# PDB_Schem.net
KiCad netlist of a schematic drawn in Altium Designer
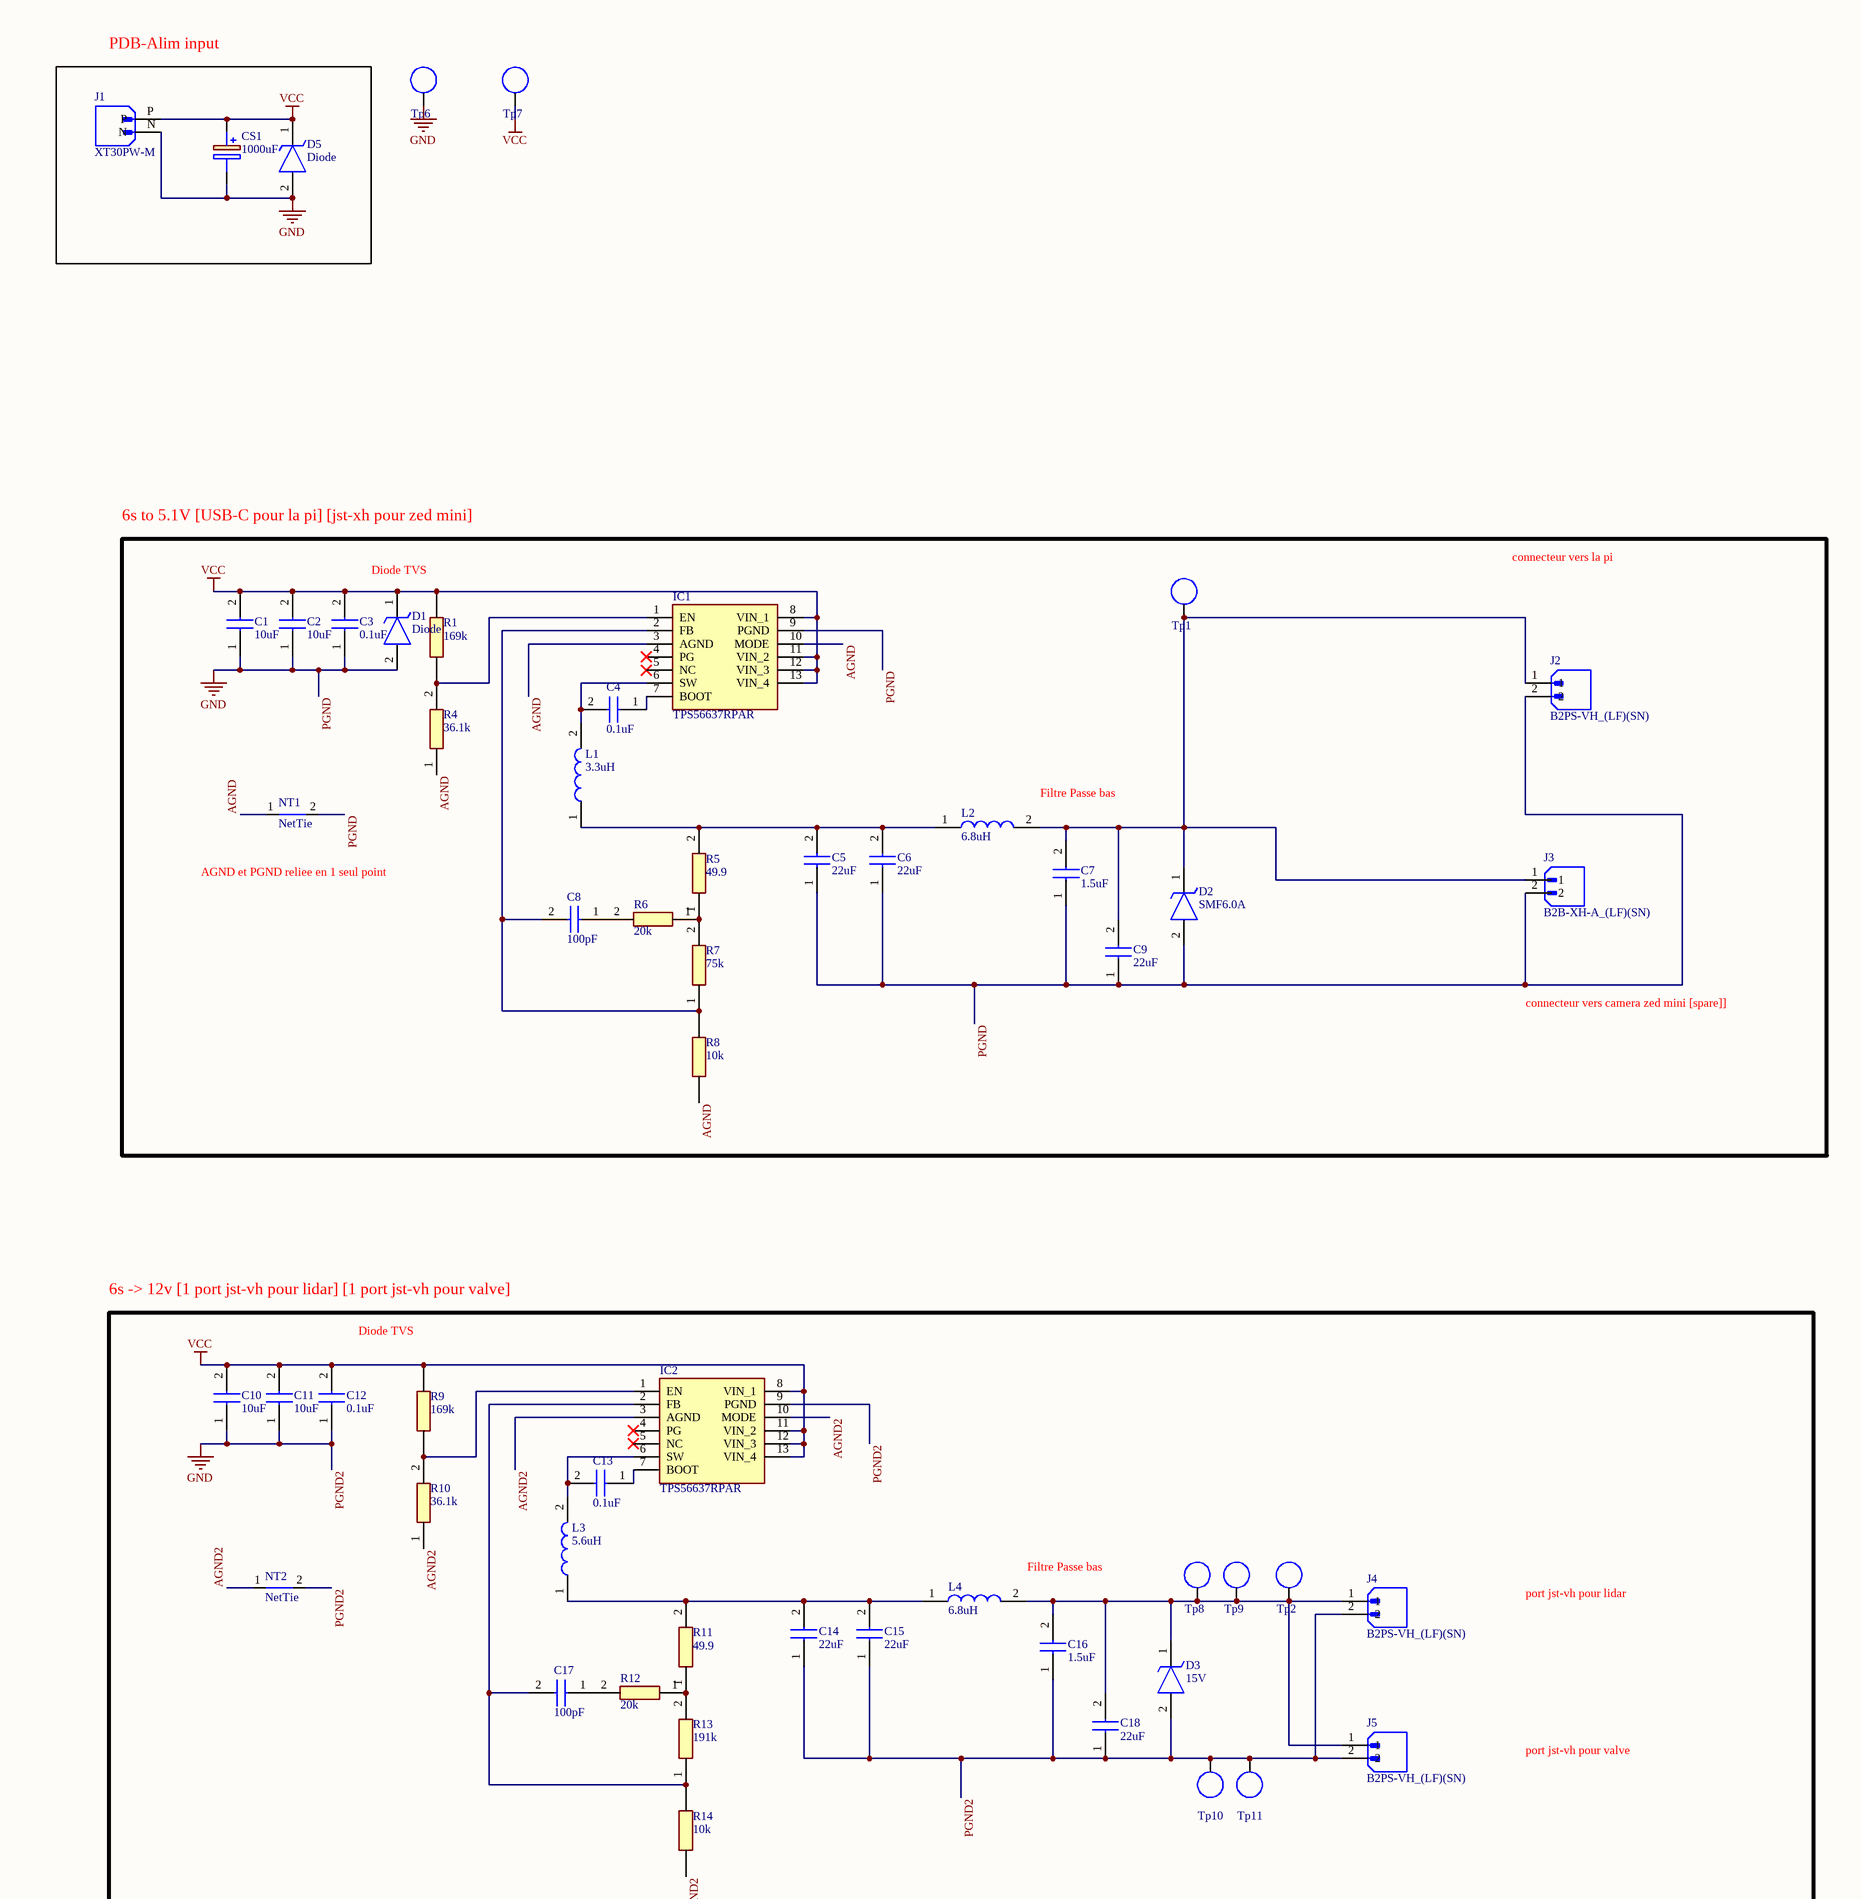
[diagram p0: PDB Schem.SchDoc, top]
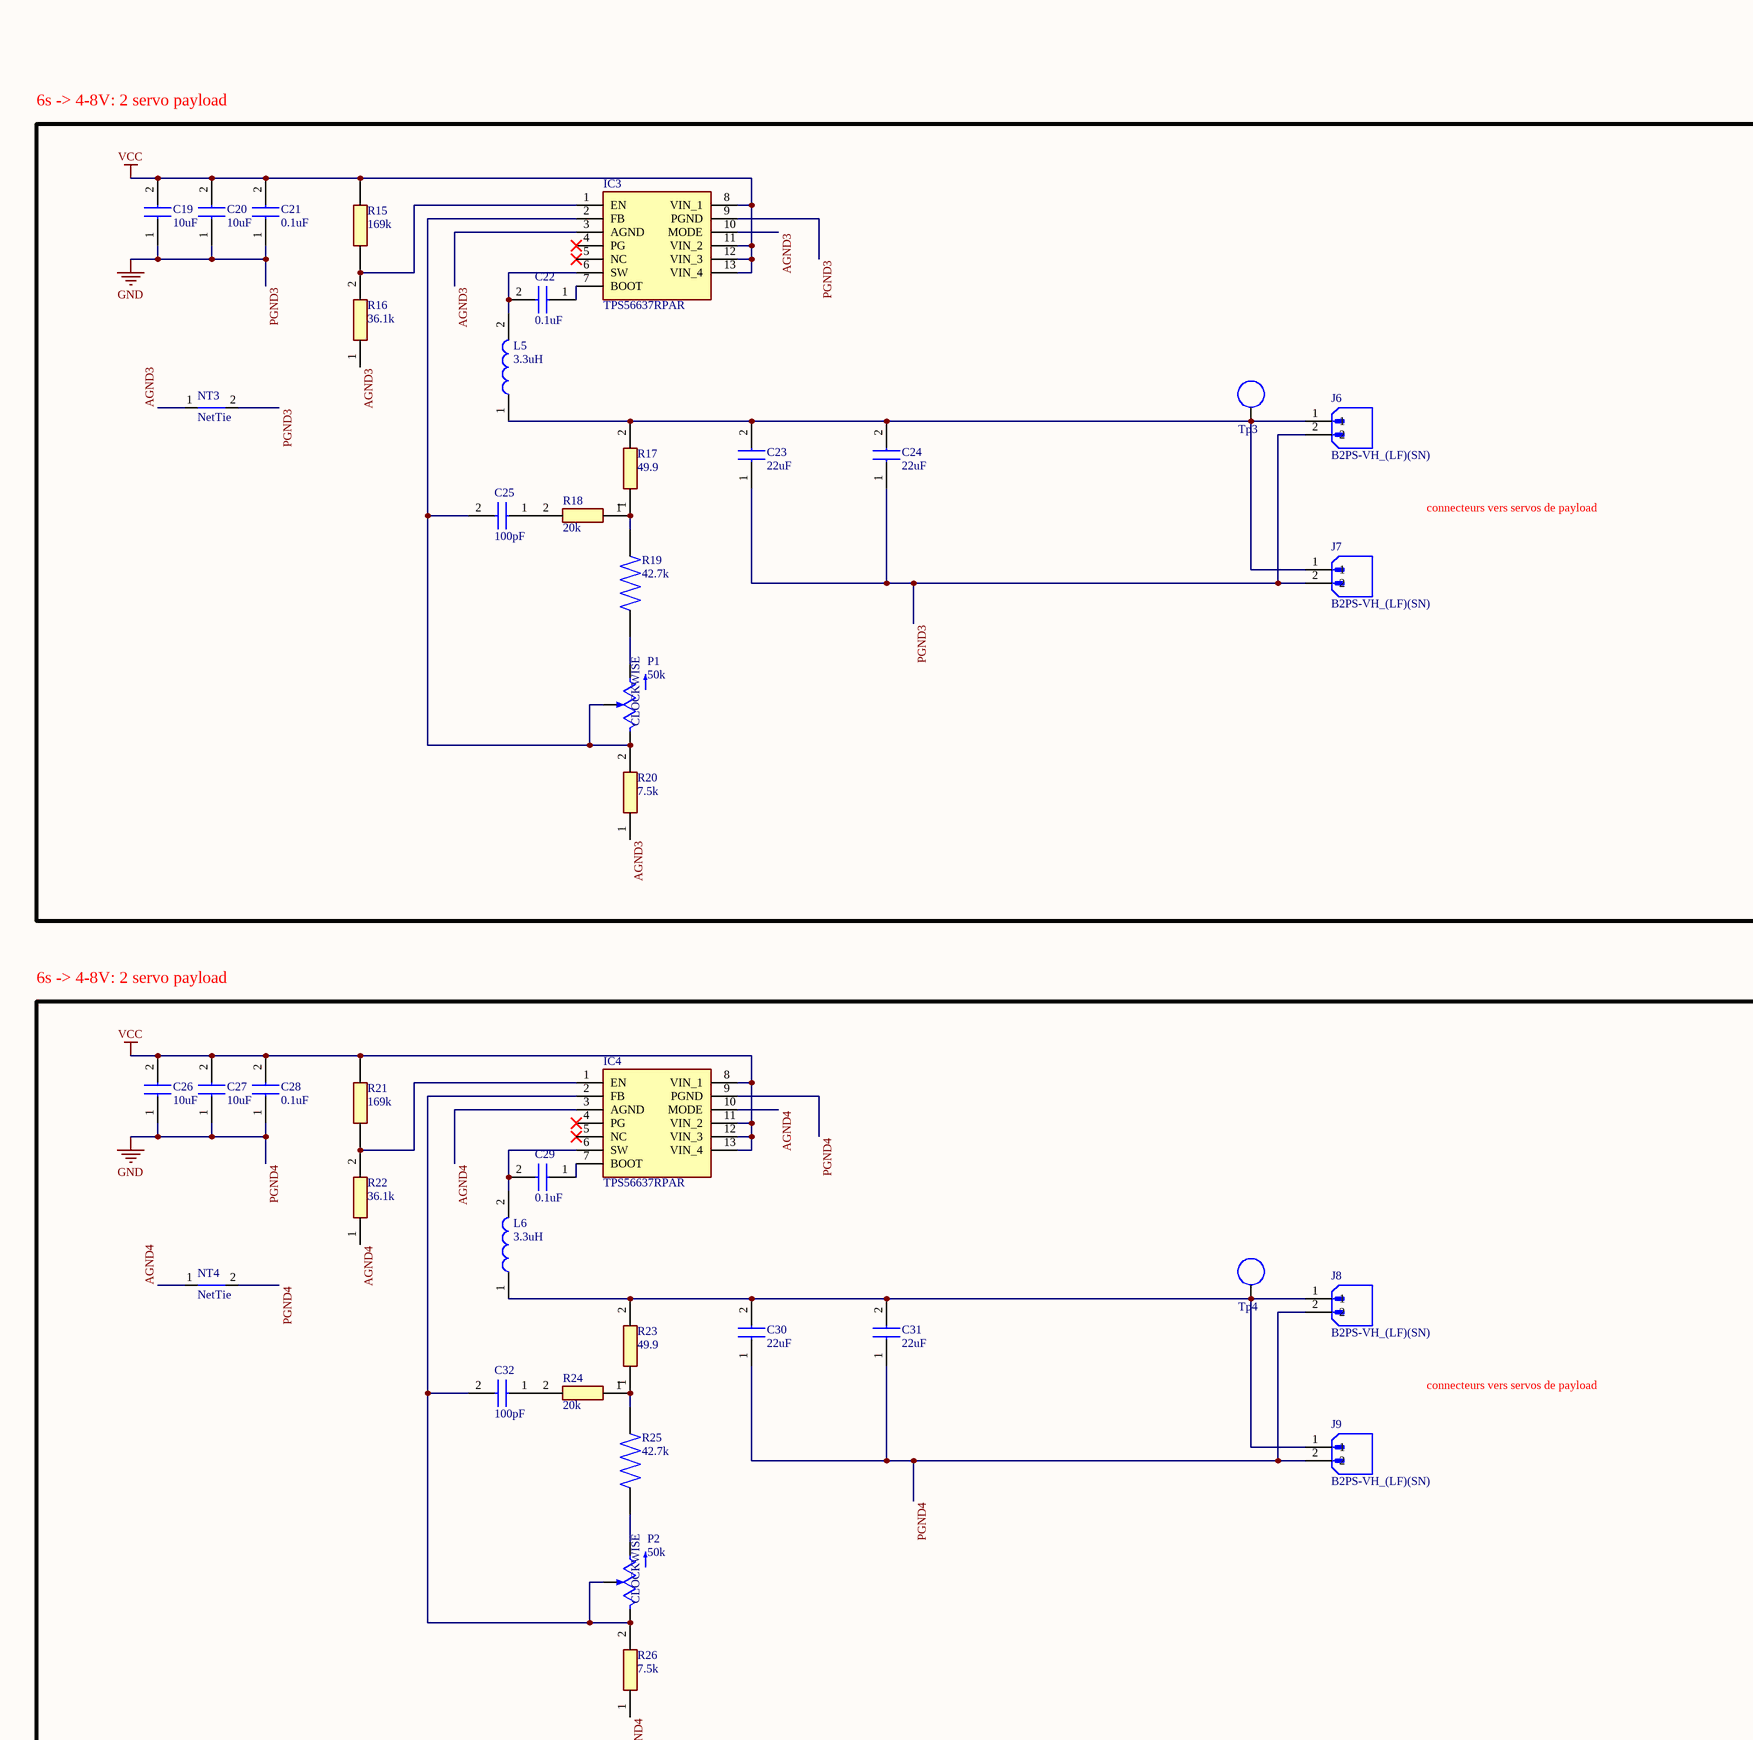
[diagram p1: PDB Schem.SchDoc, centre]
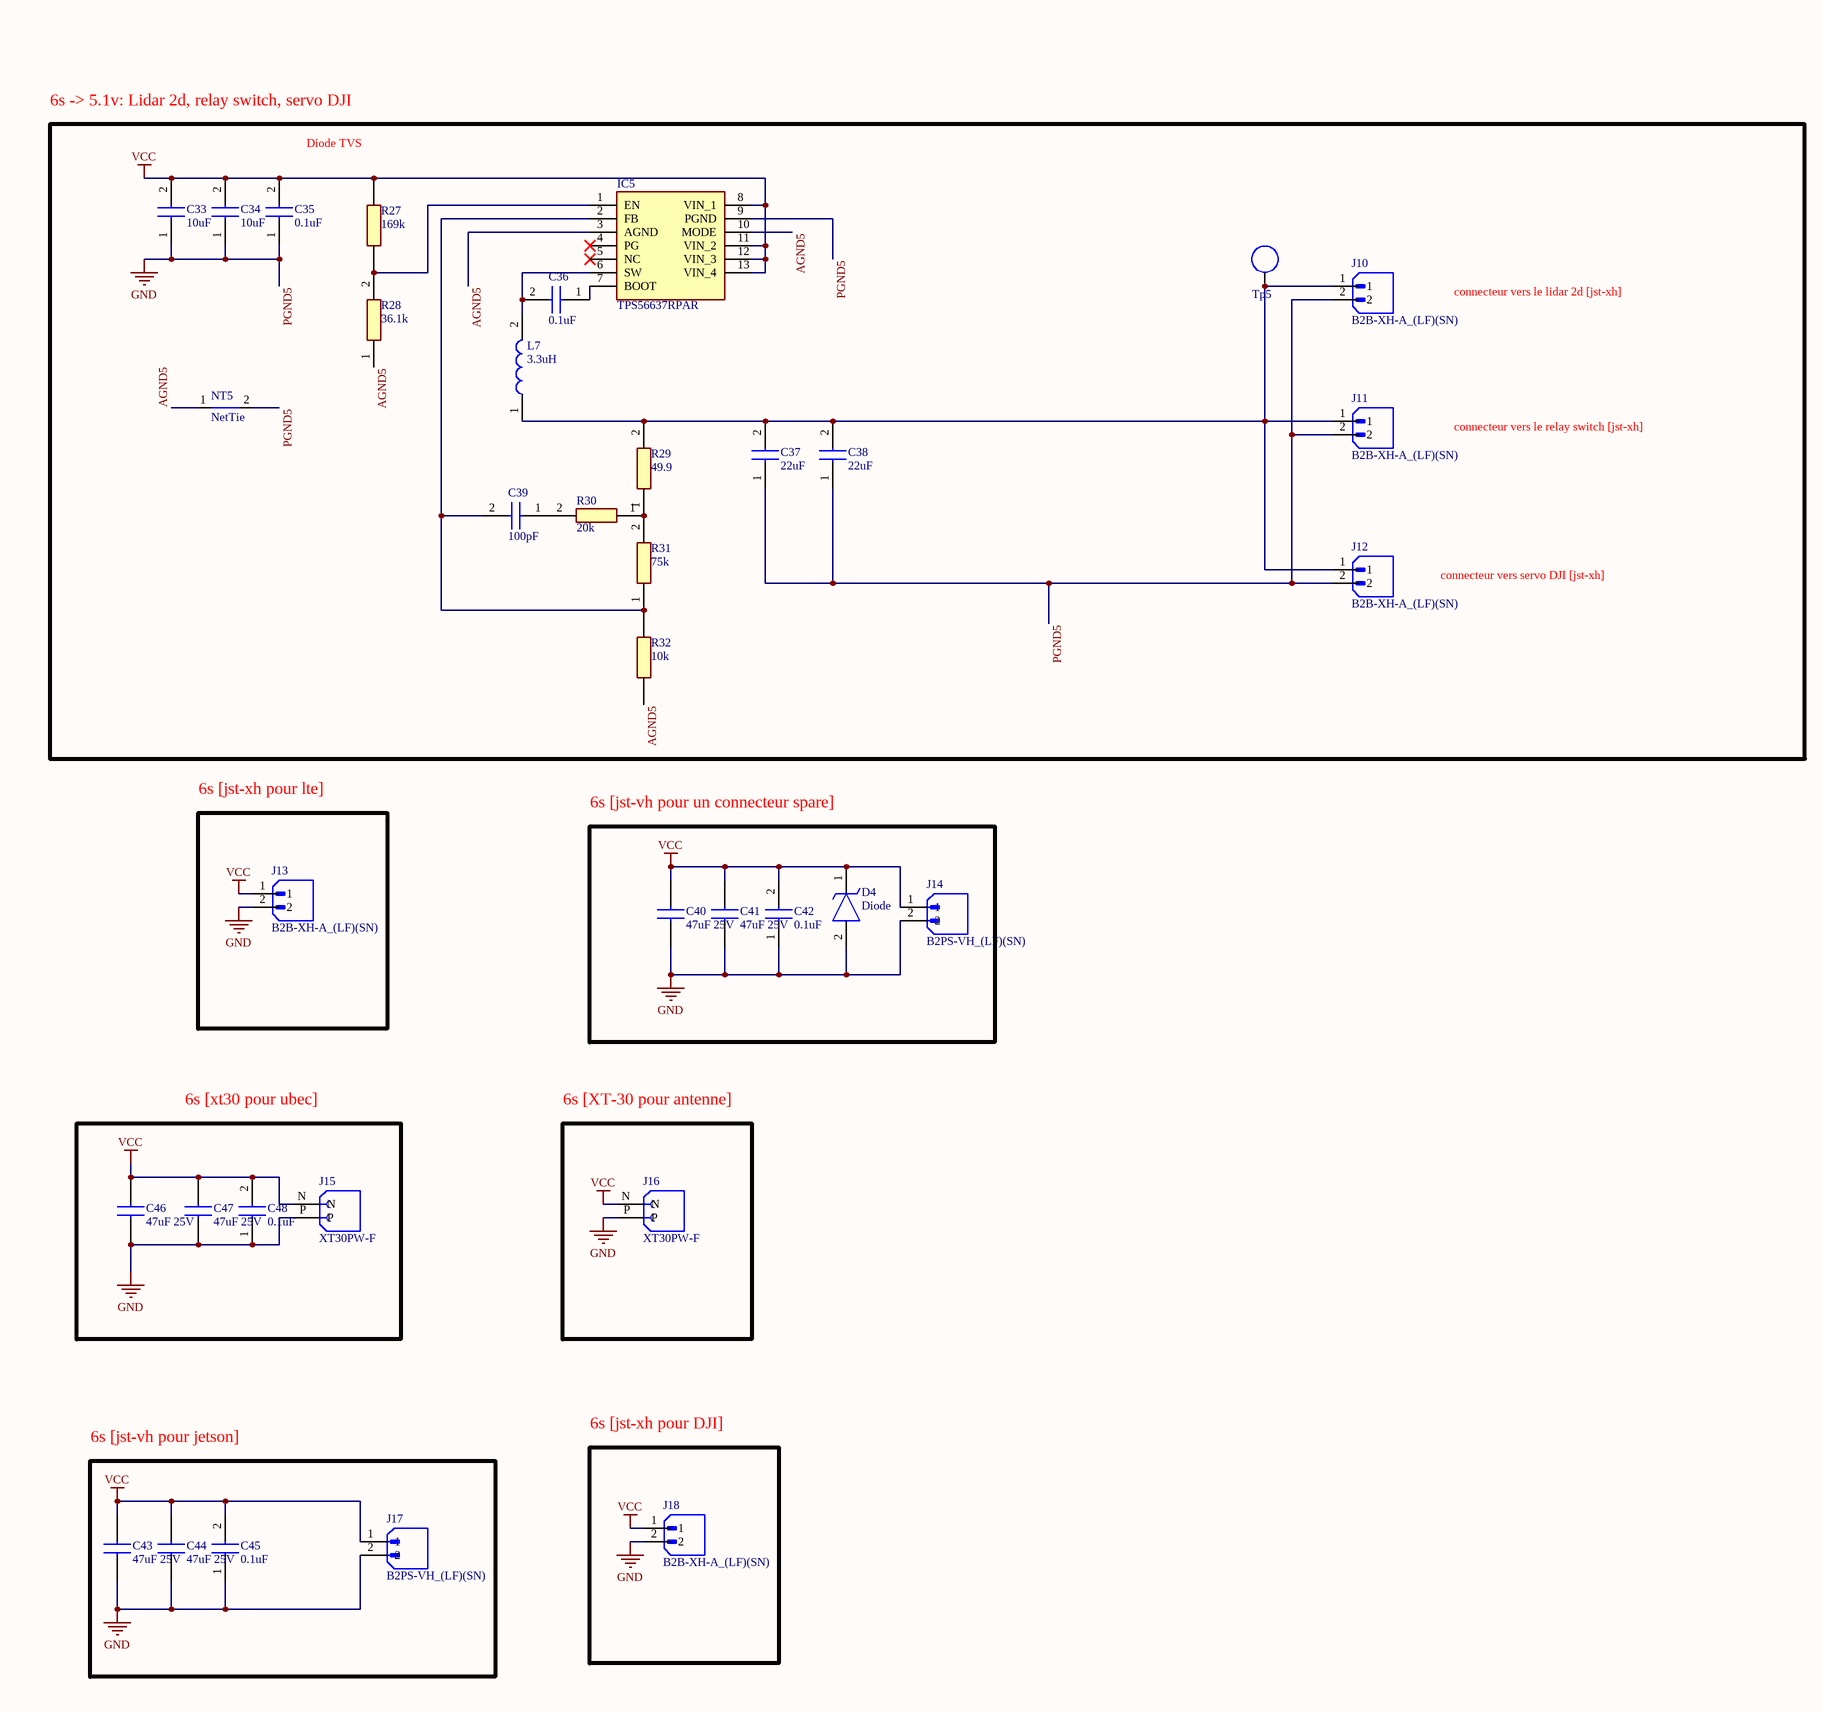
[diagram p2: PDB Schem.SchDoc, bottom]

(export (version "E")
  (design (tool "Eeschema 10.0.6"))
  (components
    (comp (ref "C1")
      (value "10uF")
      (footprint "CAPC3225X280N")
      (description "Capacitor")
      (fields (field (name "MANUFACTURER_PART_NUMBER") "AGC1210X7R500-106KNE"))
      (libsource (lib "Symbol_library") (part "AGC1210X7R500-106KNE"))
    )
    (comp (ref "C2")
      (value "10uF")
      (footprint "CAPC3225X280N")
      (description "Capacitor")
      (fields (field (name "MANUFACTURER_PART_NUMBER") "AGC1210X7R500-106KNE"))
      (libsource (lib "Symbol_library") (part "AGC1210X7R500-106KNE"))
    )
    (comp (ref "C3")
      (value "0.1uF")
      (footprint "C0603")
      (description "Capacitor")
      (fields
        (field (name "MANUFACTURER_PART_NUMBER") "C0603C104K5RACTU")
        (field (name "MOUSER PART NUMBER") "80-C0603C104K5R")
      )
      (libsource (lib "Symbol_library") (part "C0603C104K5RACTU"))
    )
    (comp (ref "C4")
      (value "0.1uF")
      (footprint "C0603")
      (description "Capacitor")
      (fields
        (field (name "MANUFACTURER_PART_NUMBER") "C0603C104K5RACTU")
        (field (name "MOUSER PART NUMBER") "80-C0603C104K5R")
      )
      (libsource (lib "Symbol_library") (part "C0603C104K5RACTU"))
    )
    (comp (ref "C5")
      (value "22uF")
      (footprint "CAPC2012X145N")
      (description "Capacitor, 35V")
      (fields
        (field (name "MANUFACTURER_PART_NUMBER") "C2012X5R1V226M125AC")
        (field (name "MOUSER PART NUMBER") "810-C2012X5R1V226MAC")
      )
      (libsource (lib "Symbol_library") (part "C2012X5R1V226M125AC"))
    )
    (comp (ref "C6")
      (value "22uF")
      (footprint "CAPC2012X145N")
      (description "Capacitor, 35V")
      (fields
        (field (name "MANUFACTURER_PART_NUMBER") "C2012X5R1V226M125AC")
        (field (name "MOUSER PART NUMBER") "810-C2012X5R1V226MAC")
      )
      (libsource (lib "Symbol_library") (part "C2012X5R1V226M125AC"))
    )
    (comp (ref "C7")
      (value "1.5uF")
      (footprint "CAPC3225X200N")
      (description "Capacitor")
      (fields
        (field (name "MANUFACTURER_PART_NUMBER") "C3225X7R2A155K200AB")
        (field (name "MOUSER PART NUMBER") "810-C3225X7R2A155K2B")
      )
      (libsource (lib "Symbol_library") (part "C3225X7R2A155K200AB"))
    )
    (comp (ref "C8")
      (value "100pF")
      (footprint "GRM1885C1H101JA01D")
      (description "Capacitor")
      (fields
        (field (name "MANUFACTURER_PART_NUMBER") "GRM1885C1H101JA01D")
        (field (name "MOUSER PART NUMBER") "81-GRM39C101J50")
      )
      (libsource (lib "Symbol_library") (part "GRM1885C1H101JA01D"))
    )
    (comp (ref "C9")
      (value "22uF")
      (footprint "CAPC2012X145N")
      (description "Capacitor, 35V")
      (fields
        (field (name "MANUFACTURER_PART_NUMBER") "C2012X5R1V226M125AC")
        (field (name "MOUSER PART NUMBER") "810-C2012X5R1V226MAC")
      )
      (libsource (lib "Symbol_library") (part "C2012X5R1V226M125AC"))
    )
    (comp (ref "C10")
      (value "10uF")
      (footprint "CAPC3225X280N")
      (description "Capacitor")
      (fields (field (name "MANUFACTURER_PART_NUMBER") "AGC1210X7R500-106KNE"))
      (libsource (lib "Symbol_library") (part "AGC1210X7R500-106KNE"))
    )
    (comp (ref "C11")
      (value "10uF")
      (footprint "CAPC3225X280N")
      (description "Capacitor")
      (fields (field (name "MANUFACTURER_PART_NUMBER") "AGC1210X7R500-106KNE"))
      (libsource (lib "Symbol_library") (part "AGC1210X7R500-106KNE"))
    )
    (comp (ref "C12")
      (value "0.1uF")
      (footprint "C0603")
      (description "Capacitor")
      (fields
        (field (name "MANUFACTURER_PART_NUMBER") "C0603C104K5RACTU")
        (field (name "MOUSER PART NUMBER") "80-C0603C104K5R")
      )
      (libsource (lib "Symbol_library") (part "C0603C104K5RACTU"))
    )
    (comp (ref "C13")
      (value "0.1uF")
      (footprint "C0603")
      (description "Capacitor")
      (fields
        (field (name "MANUFACTURER_PART_NUMBER") "C0603C104K5RACTU")
        (field (name "MOUSER PART NUMBER") "80-C0603C104K5R")
      )
      (libsource (lib "Symbol_library") (part "C0603C104K5RACTU"))
    )
    (comp (ref "C14")
      (value "22uF")
      (footprint "CAPC2012X145N")
      (description "Capacitor, 35V")
      (fields
        (field (name "MANUFACTURER_PART_NUMBER") "C2012X5R1V226M125AC")
        (field (name "MOUSER PART NUMBER") "810-C2012X5R1V226MAC")
      )
      (libsource (lib "Symbol_library") (part "C2012X5R1V226M125AC"))
    )
    (comp (ref "C15")
      (value "22uF")
      (footprint "CAPC2012X145N")
      (description "Capacitor, 35V")
      (fields
        (field (name "MANUFACTURER_PART_NUMBER") "C2012X5R1V226M125AC")
        (field (name "MOUSER PART NUMBER") "810-C2012X5R1V226MAC")
      )
      (libsource (lib "Symbol_library") (part "C2012X5R1V226M125AC"))
    )
    (comp (ref "C16")
      (value "1.5uF")
      (footprint "CAPC3225X200N")
      (description "Capacitor")
      (fields
        (field (name "MANUFACTURER_PART_NUMBER") "C3225X7R2A155K200AB")
        (field (name "MOUSER PART NUMBER") "810-C3225X7R2A155K2B")
      )
      (libsource (lib "Symbol_library") (part "C3225X7R2A155K200AB"))
    )
    (comp (ref "C17")
      (value "100pF")
      (footprint "GRM1885C1H101JA01D")
      (description "Capacitor")
      (fields
        (field (name "MANUFACTURER_PART_NUMBER") "GRM1885C1H101JA01D")
        (field (name "MOUSER PART NUMBER") "81-GRM39C101J50")
      )
      (libsource (lib "Symbol_library") (part "GRM1885C1H101JA01D"))
    )
    (comp (ref "C18")
      (value "22uF")
      (footprint "CAPC2012X145N")
      (description "Capacitor, 35V")
      (fields
        (field (name "MANUFACTURER_PART_NUMBER") "C2012X5R1V226M125AC")
        (field (name "MOUSER PART NUMBER") "810-C2012X5R1V226MAC")
      )
      (libsource (lib "Symbol_library") (part "C2012X5R1V226M125AC"))
    )
    (comp (ref "C19")
      (value "10uF")
      (footprint "CAPC3225X280N")
      (description "Capacitor")
      (fields (field (name "MANUFACTURER_PART_NUMBER") "AGC1210X7R500-106KNE"))
      (libsource (lib "Symbol_library") (part "AGC1210X7R500-106KNE"))
    )
    (comp (ref "C20")
      (value "10uF")
      (footprint "CAPC3225X280N")
      (description "Capacitor")
      (fields (field (name "MANUFACTURER_PART_NUMBER") "AGC1210X7R500-106KNE"))
      (libsource (lib "Symbol_library") (part "AGC1210X7R500-106KNE"))
    )
    (comp (ref "C21")
      (value "0.1uF")
      (footprint "C0603")
      (description "Capacitor")
      (fields
        (field (name "MANUFACTURER_PART_NUMBER") "C0603C104K5RACTU")
        (field (name "MOUSER PART NUMBER") "80-C0603C104K5R")
      )
      (libsource (lib "Symbol_library") (part "C0603C104K5RACTU"))
    )
    (comp (ref "C22")
      (value "0.1uF")
      (footprint "C0603")
      (description "Capacitor")
      (fields
        (field (name "MANUFACTURER_PART_NUMBER") "C0603C104K5RACTU")
        (field (name "MOUSER PART NUMBER") "80-C0603C104K5R")
      )
      (libsource (lib "Symbol_library") (part "C0603C104K5RACTU"))
    )
    (comp (ref "C23")
      (value "22uF")
      (footprint "CAPC2012X145N")
      (description "Capacitor, 35V")
      (fields
        (field (name "MANUFACTURER_PART_NUMBER") "C2012X5R1V226M125AC")
        (field (name "MOUSER PART NUMBER") "810-C2012X5R1V226MAC")
      )
      (libsource (lib "Symbol_library") (part "C2012X5R1V226M125AC"))
    )
    (comp (ref "C24")
      (value "22uF")
      (footprint "CAPC2012X145N")
      (description "Capacitor, 35V")
      (fields
        (field (name "MANUFACTURER_PART_NUMBER") "C2012X5R1V226M125AC")
        (field (name "MOUSER PART NUMBER") "810-C2012X5R1V226MAC")
      )
      (libsource (lib "Symbol_library") (part "C2012X5R1V226M125AC"))
    )
    (comp (ref "C25")
      (value "100pF")
      (footprint "GRM1885C1H101JA01D")
      (description "Capacitor")
      (fields
        (field (name "MANUFACTURER_PART_NUMBER") "GRM1885C1H101JA01D")
        (field (name "MOUSER PART NUMBER") "81-GRM39C101J50")
      )
      (libsource (lib "Symbol_library") (part "GRM1885C1H101JA01D"))
    )
    (comp (ref "C26")
      (value "10uF")
      (footprint "CAPC3225X280N")
      (description "Capacitor")
      (fields (field (name "MANUFACTURER_PART_NUMBER") "AGC1210X7R500-106KNE"))
      (libsource (lib "Symbol_library") (part "AGC1210X7R500-106KNE"))
    )
    (comp (ref "C27")
      (value "10uF")
      (footprint "CAPC3225X280N")
      (description "Capacitor")
      (fields (field (name "MANUFACTURER_PART_NUMBER") "AGC1210X7R500-106KNE"))
      (libsource (lib "Symbol_library") (part "AGC1210X7R500-106KNE"))
    )
    (comp (ref "C28")
      (value "0.1uF")
      (footprint "C0603")
      (description "Capacitor")
      (fields
        (field (name "MANUFACTURER_PART_NUMBER") "C0603C104K5RACTU")
        (field (name "MOUSER PART NUMBER") "80-C0603C104K5R")
      )
      (libsource (lib "Symbol_library") (part "C0603C104K5RACTU"))
    )
    (comp (ref "C29")
      (value "0.1uF")
      (footprint "C0603")
      (description "Capacitor")
      (fields
        (field (name "MANUFACTURER_PART_NUMBER") "C0603C104K5RACTU")
        (field (name "MOUSER PART NUMBER") "80-C0603C104K5R")
      )
      (libsource (lib "Symbol_library") (part "C0603C104K5RACTU"))
    )
    (comp (ref "C30")
      (value "22uF")
      (footprint "CAPC2012X145N")
      (description "Capacitor, 35V")
      (fields
        (field (name "MANUFACTURER_PART_NUMBER") "C2012X5R1V226M125AC")
        (field (name "MOUSER PART NUMBER") "810-C2012X5R1V226MAC")
      )
      (libsource (lib "Symbol_library") (part "C2012X5R1V226M125AC"))
    )
    (comp (ref "C31")
      (value "22uF")
      (footprint "CAPC2012X145N")
      (description "Capacitor, 35V")
      (fields
        (field (name "MANUFACTURER_PART_NUMBER") "C2012X5R1V226M125AC")
        (field (name "MOUSER PART NUMBER") "810-C2012X5R1V226MAC")
      )
      (libsource (lib "Symbol_library") (part "C2012X5R1V226M125AC"))
    )
    (comp (ref "C32")
      (value "100pF")
      (footprint "GRM1885C1H101JA01D")
      (description "Capacitor")
      (fields
        (field (name "MANUFACTURER_PART_NUMBER") "GRM1885C1H101JA01D")
        (field (name "MOUSER PART NUMBER") "81-GRM39C101J50")
      )
      (libsource (lib "Symbol_library") (part "GRM1885C1H101JA01D"))
    )
    (comp (ref "C33")
      (value "10uF")
      (footprint "CAPC3225X280N")
      (description "Capacitor")
      (fields (field (name "MANUFACTURER_PART_NUMBER") "AGC1210X7R500-106KNE"))
      (libsource (lib "Symbol_library") (part "AGC1210X7R500-106KNE"))
    )
    (comp (ref "C34")
      (value "10uF")
      (footprint "CAPC3225X280N")
      (description "Capacitor")
      (fields (field (name "MANUFACTURER_PART_NUMBER") "AGC1210X7R500-106KNE"))
      (libsource (lib "Symbol_library") (part "AGC1210X7R500-106KNE"))
    )
    (comp (ref "C35")
      (value "0.1uF")
      (footprint "C0603")
      (description "Capacitor")
      (fields
        (field (name "MANUFACTURER_PART_NUMBER") "C0603C104K5RACTU")
        (field (name "MOUSER PART NUMBER") "80-C0603C104K5R")
      )
      (libsource (lib "Symbol_library") (part "C0603C104K5RACTU"))
    )
    (comp (ref "C36")
      (value "0.1uF")
      (footprint "C0603")
      (description "Capacitor")
      (fields
        (field (name "MANUFACTURER_PART_NUMBER") "C0603C104K5RACTU")
        (field (name "MOUSER PART NUMBER") "80-C0603C104K5R")
      )
      (libsource (lib "Symbol_library") (part "C0603C104K5RACTU"))
    )
    (comp (ref "C37")
      (value "22uF")
      (footprint "CAPC2012X145N")
      (description "Capacitor, 35V")
      (fields
        (field (name "MANUFACTURER_PART_NUMBER") "C2012X5R1V226M125AC")
        (field (name "MOUSER PART NUMBER") "810-C2012X5R1V226MAC")
      )
      (libsource (lib "Symbol_library") (part "C2012X5R1V226M125AC"))
    )
    (comp (ref "C38")
      (value "22uF")
      (footprint "CAPC2012X145N")
      (description "Capacitor, 35V")
      (fields
        (field (name "MANUFACTURER_PART_NUMBER") "C2012X5R1V226M125AC")
        (field (name "MOUSER PART NUMBER") "810-C2012X5R1V226MAC")
      )
      (libsource (lib "Symbol_library") (part "C2012X5R1V226M125AC"))
    )
    (comp (ref "C39")
      (value "100pF")
      (footprint "GRM1885C1H101JA01D")
      (description "Capacitor")
      (fields
        (field (name "MANUFACTURER_PART_NUMBER") "GRM1885C1H101JA01D")
        (field (name "MOUSER PART NUMBER") "81-GRM39C101J50")
      )
      (libsource (lib "Symbol_library") (part "GRM1885C1H101JA01D"))
    )
    (comp (ref "C40")
      (value "47uF 25V")
      (footprint "CAPC3216X180N")
      (description "Capacitor 47 uF")
      (fields (field (name "MANUFACTURER_PART_NUMBER") "C3216X5R1E476M160AC."))
      (libsource (lib "Symbol_library") (part "C3216X5R1E476M160AC"))
    )
    (comp (ref "C41")
      (value "47uF 25V")
      (footprint "CAPC3216X180N")
      (description "Capacitor 47 uF")
      (fields (field (name "MANUFACTURER_PART_NUMBER") "C3216X5R1E476M160AC."))
      (libsource (lib "Symbol_library") (part "C3216X5R1E476M160AC"))
    )
    (comp (ref "C42")
      (value "0.1uF")
      (footprint "C0603")
      (description "Capacitor")
      (fields
        (field (name "MANUFACTURER_PART_NUMBER") "C0603C104K5RACTU")
        (field (name "MOUSER PART NUMBER") "80-C0603C104K5R")
      )
      (libsource (lib "Symbol_library") (part "C0603C104K5RACTU"))
    )
    (comp (ref "C43")
      (value "47uF 25V")
      (footprint "CAPC3216X180N")
      (description "Capacitor 47 uF")
      (fields (field (name "MANUFACTURER_PART_NUMBER") "C3216X5R1E476M160AC."))
      (libsource (lib "Symbol_library") (part "C3216X5R1E476M160AC"))
    )
    (comp (ref "C44")
      (value "47uF 25V")
      (footprint "CAPC3216X180N")
      (description "Capacitor 47 uF")
      (fields (field (name "MANUFACTURER_PART_NUMBER") "C3216X5R1E476M160AC."))
      (libsource (lib "Symbol_library") (part "C3216X5R1E476M160AC"))
    )
    (comp (ref "C45")
      (value "0.1uF")
      (footprint "C0603")
      (description "Capacitor")
      (fields
        (field (name "MANUFACTURER_PART_NUMBER") "C0603C104K5RACTU")
        (field (name "MOUSER PART NUMBER") "80-C0603C104K5R")
      )
      (libsource (lib "Symbol_library") (part "C0603C104K5RACTU"))
    )
    (comp (ref "C46")
      (value "47uF 25V")
      (footprint "CAPC3216X180N")
      (description "Capacitor 47 uF")
      (fields (field (name "MANUFACTURER_PART_NUMBER") "C3216X5R1E476M160AC."))
      (libsource (lib "Symbol_library") (part "C3216X5R1E476M160AC"))
    )
    (comp (ref "C47")
      (value "47uF 25V")
      (footprint "CAPC3216X180N")
      (description "Capacitor 47 uF")
      (fields (field (name "MANUFACTURER_PART_NUMBER") "C3216X5R1E476M160AC."))
      (libsource (lib "Symbol_library") (part "C3216X5R1E476M160AC"))
    )
    (comp (ref "C48")
      (value "0.1uF")
      (footprint "C0603")
      (description "Capacitor")
      (fields
        (field (name "MANUFACTURER_PART_NUMBER") "C0603C104K5RACTU")
        (field (name "MOUSER PART NUMBER") "80-C0603C104K5R")
      )
      (libsource (lib "Symbol_library") (part "C0603C104K5RACTU"))
    )
    (comp (ref "CS1")
      (value "1000uF")
      (footprint "CAPPRD500W60D1025H2150")
      (description "Capacitor Polarised")
      (fields
        (field (name "MANUFACTURER_PART_NUMBER") "35PX1000MEFC10X20")
        (field (name "MOUSER PART NUMBER") "232-35PX1000MEFC10X2")
      )
      (libsource (lib "Symbol_library") (part "35PX1000MEFC10X20"))
    )
    (comp (ref "D1")
      (value "Diode")
      (footprint "DIOM5436X244N")
      (description "TVS Diode (Uni-directional)")
      (fields
        (field (name "MANUFACTURER_PART_NUMBER") "SMBJ26A")
        (field (name "MOUSER PART NUMBER") "652-SMBJ26A")
      )
      (libsource (lib "Symbol_library") (part "SMBJ26A"))
    )
    (comp (ref "D2")
      (value "SMF6.0A")
      (footprint "Footprint_library:SODFL3718X140N")
      (description "TVS Diode (Uni-directional)")
      (fields (field (name "MOUSER PART NUMBER") "637-SMF6.0A"))
      (libsource (lib "Symbol_library") (part "SMF6.0A"))
    )
    (comp (ref "D3")
      (value "15V")
      (footprint "Footprint_library:DIOM5436X244N")
      (description "TVS Diode (Uni-directional)")
      (fields
        (field (name "MANUFACTURER_PART_NUMBER") "SMBJ15A")
        (field (name "MOUSER PART NUMBER") "78-SMBJ15A")
      )
      (libsource (lib "Symbol_library") (part "SMBJ15A"))
    )
    (comp (ref "D4")
      (value "Diode")
      (footprint "DIOM5436X244N")
      (description "TVS Diode (Uni-directional)")
      (fields
        (field (name "MANUFACTURER_PART_NUMBER") "SMBJ26A")
        (field (name "MOUSER PART NUMBER") "652-SMBJ26A")
      )
      (libsource (lib "Symbol_library") (part "SMBJ26A"))
    )
    (comp (ref "D5")
      (value "Diode")
      (footprint "DIOM5436X244N")
      (description "TVS Diode (Uni-directional)")
      (fields
        (field (name "MANUFACTURER_PART_NUMBER") "SMBJ26A")
        (field (name "MOUSER PART NUMBER") "652-SMBJ26A")
      )
      (libsource (lib "Symbol_library") (part "SMBJ26A"))
    )
    (comp (ref "IC1")
      (value "TPS56637RPAR")
      (footprint "TPS56637RPAR")
      (description "Integrated Circuit")
      (fields (field (name "MOUSER PART NUMBER") "595-TPS56637RPAR"))
      (libsource (lib "Symbol_library") (part "TPS56637RPAR"))
    )
    (comp (ref "IC2")
      (value "TPS56637RPAR")
      (footprint "TPS56637RPAR")
      (description "Integrated Circuit")
      (fields (field (name "MOUSER PART NUMBER") "595-TPS56637RPAR"))
      (libsource (lib "Symbol_library") (part "TPS56637RPAR"))
    )
    (comp (ref "IC3")
      (value "TPS56637RPAR")
      (footprint "TPS56637RPAR")
      (description "Integrated Circuit")
      (fields (field (name "MOUSER PART NUMBER") "595-TPS56637RPAR"))
      (libsource (lib "Symbol_library") (part "TPS56637RPAR"))
    )
    (comp (ref "IC4")
      (value "TPS56637RPAR")
      (footprint "TPS56637RPAR")
      (description "Integrated Circuit")
      (fields (field (name "MOUSER PART NUMBER") "595-TPS56637RPAR"))
      (libsource (lib "Symbol_library") (part "TPS56637RPAR"))
    )
    (comp (ref "IC5")
      (value "TPS56637RPAR")
      (footprint "TPS56637RPAR")
      (description "Integrated Circuit")
      (fields (field (name "MOUSER PART NUMBER") "595-TPS56637RPAR"))
      (libsource (lib "Symbol_library") (part "TPS56637RPAR"))
    )
    (comp (ref "J1")
      (value "XT30PW-M")
      (footprint "AMASS_XT30PW-M")
      (description "Socket; DC supply; XT30; male; PIN: 2; on PCBs; THT; Colour: yellow")
      (fields (field (name "MF") "AMASS"))
      (libsource (lib "Symbol_library") (part "XT30PW-M"))
    )
    (comp (ref "J2")
      (value "B2PS-VH_(LF)(SN)")
      (footprint "JST_B2PS-VH_(LF)(SN)")
      (description "Connector Header Through Hole, Right Angle 2 position 0.156 (3.96mm)")
      (fields (field (name "MF") "JST") (field (name "MP") "B2PS-VH (LF)(SN)"))
      (libsource (lib "Symbol_library") (part "B2PS-VH_(LF)(SN)"))
    )
    (comp (ref "J3")
      (value "B2B-XH-A_(LF)(SN)")
      (footprint "JST_B2B-XH-A_(LF)(SN)")
      (description "Connector Header Through Hole 2 position 0.098 (2.50mm)")
      (fields (field (name "MF") "JST Sales") (field (name "MP") "B2B-XH-A (LF)(SN)"))
      (libsource (lib "Symbol_library") (part "B2B-XH-A_(LF)(SN)"))
    )
    (comp (ref "J4")
      (value "B2PS-VH_(LF)(SN)")
      (footprint "JST_B2PS-VH_(LF)(SN)")
      (description "Connector Header Through Hole, Right Angle 2 position 0.156 (3.96mm)")
      (fields (field (name "MF") "JST") (field (name "MP") "B2PS-VH (LF)(SN)"))
      (libsource (lib "Symbol_library") (part "B2PS-VH_(LF)(SN)"))
    )
    (comp (ref "J5")
      (value "B2PS-VH_(LF)(SN)")
      (footprint "JST_B2PS-VH_(LF)(SN)")
      (description "Connector Header Through Hole, Right Angle 2 position 0.156 (3.96mm)")
      (fields (field (name "MF") "JST") (field (name "MP") "B2PS-VH (LF)(SN)"))
      (libsource (lib "Symbol_library") (part "B2PS-VH_(LF)(SN)"))
    )
    (comp (ref "J6")
      (value "B2PS-VH_(LF)(SN)")
      (footprint "JST_B2PS-VH_(LF)(SN)")
      (description "Connector Header Through Hole, Right Angle 2 position 0.156 (3.96mm)")
      (fields (field (name "MF") "JST") (field (name "MP") "B2PS-VH (LF)(SN)"))
      (libsource (lib "Symbol_library") (part "B2PS-VH_(LF)(SN)"))
    )
    (comp (ref "J7")
      (value "B2PS-VH_(LF)(SN)")
      (footprint "JST_B2PS-VH_(LF)(SN)")
      (description "Connector Header Through Hole, Right Angle 2 position 0.156 (3.96mm)")
      (fields (field (name "MF") "JST") (field (name "MP") "B2PS-VH (LF)(SN)"))
      (libsource (lib "Symbol_library") (part "B2PS-VH_(LF)(SN)"))
    )
    (comp (ref "J8")
      (value "B2PS-VH_(LF)(SN)")
      (footprint "JST_B2PS-VH_(LF)(SN)")
      (description "Connector Header Through Hole, Right Angle 2 position 0.156 (3.96mm)")
      (fields (field (name "MF") "JST") (field (name "MP") "B2PS-VH (LF)(SN)"))
      (libsource (lib "Symbol_library") (part "B2PS-VH_(LF)(SN)"))
    )
    (comp (ref "J9")
      (value "B2PS-VH_(LF)(SN)")
      (footprint "JST_B2PS-VH_(LF)(SN)")
      (description "Connector Header Through Hole, Right Angle 2 position 0.156 (3.96mm)")
      (fields (field (name "MF") "JST") (field (name "MP") "B2PS-VH (LF)(SN)"))
      (libsource (lib "Symbol_library") (part "B2PS-VH_(LF)(SN)"))
    )
    (comp (ref "J10")
      (value "B2B-XH-A_(LF)(SN)")
      (footprint "JST_B2B-XH-A_(LF)(SN)")
      (description "Connector Header Through Hole 2 position 0.098 (2.50mm)")
      (fields (field (name "MF") "JST Sales") (field (name "MP") "B2B-XH-A (LF)(SN)"))
      (libsource (lib "Symbol_library") (part "B2B-XH-A_(LF)(SN)"))
    )
    (comp (ref "J11")
      (value "B2B-XH-A_(LF)(SN)")
      (footprint "JST_B2B-XH-A_(LF)(SN)")
      (description "Connector Header Through Hole 2 position 0.098 (2.50mm)")
      (fields (field (name "MF") "JST Sales") (field (name "MP") "B2B-XH-A (LF)(SN)"))
      (libsource (lib "Symbol_library") (part "B2B-XH-A_(LF)(SN)"))
    )
    (comp (ref "J12")
      (value "B2B-XH-A_(LF)(SN)")
      (footprint "JST_B2B-XH-A_(LF)(SN)")
      (description "Connector Header Through Hole 2 position 0.098 (2.50mm)")
      (fields (field (name "MF") "JST Sales") (field (name "MP") "B2B-XH-A (LF)(SN)"))
      (libsource (lib "Symbol_library") (part "B2B-XH-A_(LF)(SN)"))
    )
    (comp (ref "J13")
      (value "B2B-XH-A_(LF)(SN)")
      (footprint "JST_B2B-XH-A_(LF)(SN)")
      (description "Connector Header Through Hole 2 position 0.098 (2.50mm)")
      (fields (field (name "MF") "JST Sales") (field (name "MP") "B2B-XH-A (LF)(SN)"))
      (libsource (lib "Symbol_library") (part "B2B-XH-A_(LF)(SN)"))
    )
    (comp (ref "J14")
      (value "B2PS-VH_(LF)(SN)")
      (footprint "JST_B2PS-VH_(LF)(SN)")
      (description "Connector Header Through Hole, Right Angle 2 position 0.156 (3.96mm)")
      (fields (field (name "MF") "JST") (field (name "MP") "B2PS-VH (LF)(SN)"))
      (libsource (lib "Symbol_library") (part "B2PS-VH_(LF)(SN)"))
    )
    (comp (ref "J15")
      (value "XT30PW-F")
      (footprint "AMASS_XT30PW-F")
      (description "Socket; DC supply; XT30; female; PIN: 2; on PCBs; THT; yellow; 15A")
      (fields (field (name "MF") "amass"))
      (libsource (lib "Symbol_library") (part "XT30PW-F"))
    )
    (comp (ref "J16")
      (value "XT30PW-F")
      (footprint "AMASS_XT30PW-F")
      (description "Socket; DC supply; XT30; female; PIN: 2; on PCBs; THT; yellow; 15A")
      (fields (field (name "MF") "amass"))
      (libsource (lib "Symbol_library") (part "XT30PW-F"))
    )
    (comp (ref "J17")
      (value "B2PS-VH_(LF)(SN)")
      (footprint "JST_B2PS-VH_(LF)(SN)")
      (description "Connector Header Through Hole, Right Angle 2 position 0.156 (3.96mm)")
      (fields (field (name "MF") "JST") (field (name "MP") "B2PS-VH (LF)(SN)"))
      (libsource (lib "Symbol_library") (part "B2PS-VH_(LF)(SN)"))
    )
    (comp (ref "J18")
      (value "B2B-XH-A_(LF)(SN)")
      (footprint "JST_B2B-XH-A_(LF)(SN)")
      (description "Connector Header Through Hole 2 position 0.098 (2.50mm)")
      (fields (field (name "MF") "JST Sales") (field (name "MP") "B2B-XH-A (LF)(SN)"))
      (libsource (lib "Symbol_library") (part "B2B-XH-A_(LF)(SN)"))
    )
    (comp (ref "L1")
      (value "3.3uH")
      (footprint "Footprint_library:INDM3225X240N")
      (description "Inductor")
      (fields (field (name "MANUFACTURER_PART_NUMBER") "NLV32T-3R3J-EF"))
      (libsource (lib "Symbol_library") (part "NLV32T-3R3J-EF"))
    )
    (comp (ref "L2")
      (value "6.8uH")
      (footprint "ASPIF60606R8MT")
      (description "Inductor")
      (fields (field (name "MANUFACTURER_PART_NUMBER") "ASPI-F6060-6R8M-T"))
      (libsource (lib "Symbol_library") (part "ASPI-F6060-6R8M-T"))
    )
    (comp (ref "L3")
      (value "5.6uH")
      (footprint "Footprint_library:INDPM125125X800N")
      (description "Inductor")
      (fields
        (field (name "MANUFACTURER_PART_NUMBER") "SRR1280-5R6Y")
        (field (name "MOUSER PART NUMBER") "652-SRR1280-5R6Y")
      )
      (libsource (lib "Symbol_library") (part "SRR1280-5R6Y"))
    )
    (comp (ref "L4")
      (value "6.8uH")
      (footprint "ASPIF60606R8MT")
      (description "Inductor")
      (fields (field (name "MANUFACTURER_PART_NUMBER") "ASPI-F6060-6R8M-T"))
      (libsource (lib "Symbol_library") (part "ASPI-F6060-6R8M-T"))
    )
    (comp (ref "L5")
      (value "3.3uH")
      (footprint "Footprint_library:INDM3225X240N")
      (description "Inductor")
      (fields (field (name "MANUFACTURER_PART_NUMBER") "NLV32T-3R3J-EF"))
      (libsource (lib "Symbol_library") (part "NLV32T-3R3J-EF"))
    )
    (comp (ref "L6")
      (value "3.3uH")
      (footprint "Footprint_library:INDM3225X240N")
      (description "Inductor")
      (fields (field (name "MANUFACTURER_PART_NUMBER") "NLV32T-3R3J-EF"))
      (libsource (lib "Symbol_library") (part "NLV32T-3R3J-EF"))
    )
    (comp (ref "L7")
      (value "3.3uH")
      (footprint "Footprint_library:INDM3225X240N")
      (description "Inductor")
      (fields (field (name "MANUFACTURER_PART_NUMBER") "NLV32T-3R3J-EF"))
      (libsource (lib "Symbol_library") (part "NLV32T-3R3J-EF"))
    )
    (comp (ref "NT1")
      (value "NetTie")
      (footprint "NetTie")
      (description "Net Tie")
      (libsource (lib "Symbol_library") (part "NetTie"))
    )
    (comp (ref "NT2")
      (value "NetTie")
      (footprint "NetTie")
      (description "Net Tie")
      (libsource (lib "Symbol_library") (part "NetTie"))
    )
    (comp (ref "NT3")
      (value "NetTie")
      (footprint "NetTie")
      (description "Net Tie")
      (libsource (lib "Symbol_library") (part "NetTie"))
    )
    (comp (ref "NT4")
      (value "NetTie")
      (footprint "NetTie")
      (description "Net Tie")
      (libsource (lib "Symbol_library") (part "NetTie"))
    )
    (comp (ref "NT5")
      (value "NetTie")
      (footprint "NetTie")
      (description "Net Tie")
      (libsource (lib "Symbol_library") (part "NetTie"))
    )
    (comp (ref "P1")
      (value "50k")
      (footprint "TRIM_3361P-1-503GLF")
      (description "Potentiometer 50k ohms")
      (libsource (lib "Symbol_library") (part "TRIM_3361P-1-503GLF"))
    )
    (comp (ref "P2")
      (value "50k")
      (footprint "TRIM_3361P-1-503GLF")
      (description "Potentiometer 50k ohms")
      (libsource (lib "Symbol_library") (part "TRIM_3361P-1-503GLF"))
    )
    (comp (ref "R1")
      (value "169k")
      (footprint "RESC2012X50N")
      (description "Resistor")
      (fields
        (field (name "MANUFACTURER_PART_NUMBER") "CRCW08051K96FKEA")
        (field (name "MOUSER PART NUMBER") "71-CRCW08051K96FKEA")
      )
      (libsource (lib "Symbol_library") (part "CRCW08051K96FKEA"))
    )
    (comp (ref "R4")
      (value "36.1k")
      (footprint "Footprint_library:RESC1608X51N")
      (description "Resistor")
      (fields (field (name "MANUFACTURER_PART_NUMBER") "PTN0603E3612BST1"))
      (libsource (lib "Symbol_library") (part "PTN0603E3612BST1"))
    )
    (comp (ref "R5")
      (value "49.9")
      (footprint "RESC3016X65N")
      (description "Resistor")
      (fields
        (field (name "MANUFACTURER_PART_NUMBER") "RNCF1206TKY49R9")
        (field (name "MOUSER PART NUMBER") "708-RNCF1206TKY49R9")
      )
      (libsource (lib "Symbol_library") (part "RNCF1206TKY49R9"))
    )
    (comp (ref "R6")
      (value "20k")
      (footprint "Footprint_library:RESC2012X60N")
      (description "Resistor")
      (fields
        (field (name "MANUFACTURER_PART_NUMBER") "RK73H2ATTD2002F")
        (field (name "MOUSER PART NUMBER") "660-RK73H2ATTD2002F")
      )
      (libsource (lib "Symbol_library") (part "RK73H2ATTD2002F"))
    )
    (comp (ref "R7")
      (value "75k")
      (footprint "Footprint_library:RESC3216X75N")
      (description "Resistor")
      (fields
        (field (name "MANUFACTURER_PART_NUMBER") "CR1206-FX-7502ELF")
        (field (name "MOUSER PART NUMBER") "652-CR1206FX-7502ELF")
      )
      (libsource (lib "Symbol_library") (part "CR1206-FX-7502ELF"))
    )
    (comp (ref "R8")
      (value "10k")
      (footprint "RESC2012X60N")
      (description "Resistor")
      (fields
        (field (name "MANUFACTURER_PART_NUMBER") "CRCW080510K0FKEAHP")
        (field (name "MOUSER PART NUMBER") "71-CRCW080510K0FKEAH")
      )
      (libsource (lib "Symbol_library") (part "CRCW080510K0FKEAHP"))
    )
    (comp (ref "R9")
      (value "169k")
      (footprint "RESC2012X50N")
      (description "Resistor")
      (fields
        (field (name "MANUFACTURER_PART_NUMBER") "CRCW08051K96FKEA")
        (field (name "MOUSER PART NUMBER") "71-CRCW08051K96FKEA")
      )
      (libsource (lib "Symbol_library") (part "CRCW08051K96FKEA"))
    )
    (comp (ref "R10")
      (value "36.1k")
      (footprint "Footprint_library:RESC1608X51N")
      (description "Resistor")
      (fields (field (name "MANUFACTURER_PART_NUMBER") "PTN0603E3612BST1"))
      (libsource (lib "Symbol_library") (part "PTN0603E3612BST1"))
    )
    (comp (ref "R11")
      (value "49.9")
      (footprint "RESC3016X65N")
      (description "Resistor")
      (fields
        (field (name "MANUFACTURER_PART_NUMBER") "RNCF1206TKY49R9")
        (field (name "MOUSER PART NUMBER") "708-RNCF1206TKY49R9")
      )
      (libsource (lib "Symbol_library") (part "RNCF1206TKY49R9"))
    )
    (comp (ref "R12")
      (value "20k")
      (footprint "Footprint_library:RESC2012X60N")
      (description "Resistor")
      (fields
        (field (name "MANUFACTURER_PART_NUMBER") "RK73H2ATTD2002F")
        (field (name "MOUSER PART NUMBER") "660-RK73H2ATTD2002F")
      )
      (libsource (lib "Symbol_library") (part "RK73H2ATTD2002F"))
    )
    (comp (ref "R13")
      (value "191k")
      (footprint "Footprint_library:ERJ6ENF1000V")
      (description "Resistor")
      (fields
        (field (name "MANUFACTURER_PART_NUMBER") "ERJ-6ENF1913V")
        (field (name "MOUSER PART NUMBER") "667-ERJ-6ENF1913V")
      )
      (libsource (lib "Symbol_library") (part "ERJ-6ENF1913V"))
    )
    (comp (ref "R14")
      (value "10k")
      (footprint "RESC2012X60N")
      (description "Resistor")
      (fields
        (field (name "MANUFACTURER_PART_NUMBER") "CRCW080510K0FKEAHP")
        (field (name "MOUSER PART NUMBER") "71-CRCW080510K0FKEAH")
      )
      (libsource (lib "Symbol_library") (part "CRCW080510K0FKEAHP"))
    )
    (comp (ref "R15")
      (value "169k")
      (footprint "RESC2012X50N")
      (description "Resistor")
      (fields
        (field (name "MANUFACTURER_PART_NUMBER") "CRCW08051K96FKEA")
        (field (name "MOUSER PART NUMBER") "71-CRCW08051K96FKEA")
      )
      (libsource (lib "Symbol_library") (part "CRCW08051K96FKEA"))
    )
    (comp (ref "R16")
      (value "36.1k")
      (footprint "Footprint_library:RESC1608X51N")
      (description "Resistor")
      (fields (field (name "MANUFACTURER_PART_NUMBER") "PTN0603E3612BST1"))
      (libsource (lib "Symbol_library") (part "PTN0603E3612BST1"))
    )
    (comp (ref "R17")
      (value "49.9")
      (footprint "RESC3016X65N")
      (description "Resistor")
      (fields
        (field (name "MANUFACTURER_PART_NUMBER") "RNCF1206TKY49R9")
        (field (name "MOUSER PART NUMBER") "708-RNCF1206TKY49R9")
      )
      (libsource (lib "Symbol_library") (part "RNCF1206TKY49R9"))
    )
    (comp (ref "R18")
      (value "20k")
      (footprint "Footprint_library:RESC2012X60N")
      (description "Resistor")
      (fields
        (field (name "MANUFACTURER_PART_NUMBER") "RK73H2ATTD2002F")
        (field (name "MOUSER PART NUMBER") "660-RK73H2ATTD2002F")
      )
      (libsource (lib "Symbol_library") (part "RK73H2ATTD2002F"))
    )
    (comp (ref "R19")
      (value "42.7k")
      (footprint "RESC2012X60N")
      (fields (field (name "MP") "RN73R2ATTD4272D25"))
      (libsource (lib "Symbol_library") (part "RN73R2ATTD4272D25"))
    )
    (comp (ref "R20")
      (value "7.5k")
      (footprint "Footprint_library:RESC1608X55N")
      (description "Resistor")
      (fields
        (field (name "MANUFACTURER_PART_NUMBER") "RC0603FR-077K5L")
        (field (name "MOUSER PART NUMBER") "603-RC0603FR-077K5L")
      )
      (libsource (lib "Symbol_library") (part "RC0603FR-077K5L"))
    )
    (comp (ref "R21")
      (value "169k")
      (footprint "RESC2012X50N")
      (description "Resistor")
      (fields
        (field (name "MANUFACTURER_PART_NUMBER") "CRCW08051K96FKEA")
        (field (name "MOUSER PART NUMBER") "71-CRCW08051K96FKEA")
      )
      (libsource (lib "Symbol_library") (part "CRCW08051K96FKEA"))
    )
    (comp (ref "R22")
      (value "36.1k")
      (footprint "Footprint_library:RESC1608X51N")
      (description "Resistor")
      (fields (field (name "MANUFACTURER_PART_NUMBER") "PTN0603E3612BST1"))
      (libsource (lib "Symbol_library") (part "PTN0603E3612BST1"))
    )
    (comp (ref "R23")
      (value "49.9")
      (footprint "RESC3016X65N")
      (description "Resistor")
      (fields
        (field (name "MANUFACTURER_PART_NUMBER") "RNCF1206TKY49R9")
        (field (name "MOUSER PART NUMBER") "708-RNCF1206TKY49R9")
      )
      (libsource (lib "Symbol_library") (part "RNCF1206TKY49R9"))
    )
    (comp (ref "R24")
      (value "20k")
      (footprint "Footprint_library:RESC2012X60N")
      (description "Resistor")
      (fields
        (field (name "MANUFACTURER_PART_NUMBER") "RK73H2ATTD2002F")
        (field (name "MOUSER PART NUMBER") "660-RK73H2ATTD2002F")
      )
      (libsource (lib "Symbol_library") (part "RK73H2ATTD2002F"))
    )
    (comp (ref "R25")
      (value "42.7k")
      (footprint "RESC2012X60N")
      (fields (field (name "MP") "RN73R2ATTD4272D25"))
      (libsource (lib "Symbol_library") (part "RN73R2ATTD4272D25"))
    )
    (comp (ref "R26")
      (value "7.5k")
      (footprint "Footprint_library:RESC1608X55N")
      (description "Resistor")
      (fields
        (field (name "MANUFACTURER_PART_NUMBER") "RC0603FR-077K5L")
        (field (name "MOUSER PART NUMBER") "603-RC0603FR-077K5L")
      )
      (libsource (lib "Symbol_library") (part "RC0603FR-077K5L"))
    )
    (comp (ref "R27")
      (value "169k")
      (footprint "RESC2012X50N")
      (description "Resistor")
      (fields
        (field (name "MANUFACTURER_PART_NUMBER") "CRCW08051K96FKEA")
        (field (name "MOUSER PART NUMBER") "71-CRCW08051K96FKEA")
      )
      (libsource (lib "Symbol_library") (part "CRCW08051K96FKEA"))
    )
    (comp (ref "R28")
      (value "36.1k")
      (footprint "Footprint_library:RESC1608X51N")
      (description "Resistor")
      (fields (field (name "MANUFACTURER_PART_NUMBER") "PTN0603E3612BST1"))
      (libsource (lib "Symbol_library") (part "PTN0603E3612BST1"))
    )
    (comp (ref "R29")
      (value "49.9")
      (footprint "RESC3016X65N")
      (description "Resistor")
      (fields
        (field (name "MANUFACTURER_PART_NUMBER") "RNCF1206TKY49R9")
        (field (name "MOUSER PART NUMBER") "708-RNCF1206TKY49R9")
      )
      (libsource (lib "Symbol_library") (part "RNCF1206TKY49R9"))
    )
    (comp (ref "R30")
      (value "20k")
      (footprint "Footprint_library:RESC2012X60N")
      (description "Resistor")
      (fields
        (field (name "MANUFACTURER_PART_NUMBER") "RK73H2ATTD2002F")
        (field (name "MOUSER PART NUMBER") "660-RK73H2ATTD2002F")
      )
      (libsource (lib "Symbol_library") (part "RK73H2ATTD2002F"))
    )
    (comp (ref "R31")
      (value "75k")
      (footprint "Footprint_library:RESC3216X75N")
      (description "Resistor")
      (fields
        (field (name "MANUFACTURER_PART_NUMBER") "CR1206-FX-7502ELF")
        (field (name "MOUSER PART NUMBER") "652-CR1206FX-7502ELF")
      )
      (libsource (lib "Symbol_library") (part "CR1206-FX-7502ELF"))
    )
    (comp (ref "R32")
      (value "10k")
      (footprint "RESC2012X60N")
      (description "Resistor")
      (fields
        (field (name "MANUFACTURER_PART_NUMBER") "CRCW080510K0FKEAHP")
        (field (name "MOUSER PART NUMBER") "71-CRCW080510K0FKEAH")
      )
      (libsource (lib "Symbol_library") (part "CRCW080510K0FKEAHP"))
    )
    (comp (ref "Tp1")
      (value "Testpoint")
      (footprint "Testpoint")
      (libsource (lib "Symbol_library") (part "Testpoint"))
    )
    (comp (ref "Tp2")
      (value "Testpoint")
      (footprint "Testpoint")
      (libsource (lib "Symbol_library") (part "Testpoint"))
    )
    (comp (ref "Tp3")
      (value "Testpoint")
      (footprint "Testpoint")
      (libsource (lib "Symbol_library") (part "Testpoint"))
    )
    (comp (ref "Tp4")
      (value "Testpoint")
      (footprint "Testpoint")
      (libsource (lib "Symbol_library") (part "Testpoint"))
    )
    (comp (ref "Tp5")
      (value "Testpoint")
      (footprint "Testpoint")
      (libsource (lib "Symbol_library") (part "Testpoint"))
    )
    (comp (ref "Tp6")
      (value "Testpoint")
      (footprint "Testpoint")
      (libsource (lib "Symbol_library") (part "Testpoint"))
    )
    (comp (ref "Tp7")
      (value "Testpoint")
      (footprint "Testpoint")
      (libsource (lib "Symbol_library") (part "Testpoint"))
    )
    (comp (ref "Tp8")
      (value "Testpoint")
      (footprint "Testpoint")
      (libsource (lib "Symbol_library") (part "Testpoint"))
    )
    (comp (ref "Tp9")
      (value "Testpoint")
      (footprint "Testpoint")
      (libsource (lib "Symbol_library") (part "Testpoint"))
    )
    (comp (ref "Tp10")
      (value "Testpoint")
      (footprint "Testpoint")
      (libsource (lib "Symbol_library") (part "Testpoint"))
    )
    (comp (ref "Tp11")
      (value "Testpoint")
      (footprint "Testpoint")
      (libsource (lib "Symbol_library") (part "Testpoint"))
    )
  )
  (nets
    (net (code "1") (name "/AGND") (class "Default")
      (node (ref "IC1") (pin "10") (pinfunction "MODE_10") (pintype "passive"))
      (node (ref "IC1") (pin "3") (pinfunction "AGND_3") (pintype "passive"))
      (node (ref "NT1") (pin "1") (pintype "passive"))
      (node (ref "R4") (pin "1") (pinfunction "1_1") (pintype "passive"))
      (node (ref "R8") (pin "1") (pinfunction "1_1") (pintype "passive"))
    )
    (net (code "2") (name "/AGND2") (class "Default")
      (node (ref "IC2") (pin "10") (pinfunction "MODE_10") (pintype "passive"))
      (node (ref "IC2") (pin "3") (pinfunction "AGND_3") (pintype "passive"))
      (node (ref "NT2") (pin "1") (pintype "passive"))
      (node (ref "R10") (pin "1") (pinfunction "1_1") (pintype "passive"))
      (node (ref "R14") (pin "1") (pinfunction "1_1") (pintype "passive"))
    )
    (net (code "3") (name "/AGND3") (class "Default")
      (node (ref "IC3") (pin "10") (pinfunction "MODE_10") (pintype "passive"))
      (node (ref "IC3") (pin "3") (pinfunction "AGND_3") (pintype "passive"))
      (node (ref "NT3") (pin "1") (pintype "passive"))
      (node (ref "R16") (pin "1") (pinfunction "1_1") (pintype "passive"))
      (node (ref "R20") (pin "1") (pinfunction "1_1") (pintype "passive"))
    )
    (net (code "4") (name "/AGND4") (class "Default")
      (node (ref "IC4") (pin "10") (pinfunction "MODE_10") (pintype "passive"))
      (node (ref "IC4") (pin "3") (pinfunction "AGND_3") (pintype "passive"))
      (node (ref "NT4") (pin "1") (pintype "passive"))
      (node (ref "R22") (pin "1") (pinfunction "1_1") (pintype "passive"))
      (node (ref "R26") (pin "1") (pinfunction "1_1") (pintype "passive"))
    )
    (net (code "5") (name "/AGND5") (class "Default")
      (node (ref "IC5") (pin "10") (pinfunction "MODE_10") (pintype "passive"))
      (node (ref "IC5") (pin "3") (pinfunction "AGND_3") (pintype "passive"))
      (node (ref "NT5") (pin "1") (pintype "passive"))
      (node (ref "R28") (pin "1") (pinfunction "1_1") (pintype "passive"))
      (node (ref "R32") (pin "1") (pinfunction "1_1") (pintype "passive"))
    )
    (net (code "6") (name "GND") (class "Default")
      (node (ref "C1") (pin "1") (pinfunction "1_1") (pintype "passive"))
      (node (ref "C10") (pin "1") (pinfunction "1_1") (pintype "passive"))
      (node (ref "C11") (pin "1") (pinfunction "1_1") (pintype "passive"))
      (node (ref "C12") (pin "1") (pinfunction "1_1") (pintype "passive"))
      (node (ref "C14") (pin "1") (pinfunction "1_1") (pintype "passive"))
      (node (ref "C15") (pin "1") (pinfunction "1_1") (pintype "passive"))
      (node (ref "C16") (pin "1") (pinfunction "1_1") (pintype "passive"))
      (node (ref "C18") (pin "1") (pinfunction "1_1") (pintype "passive"))
      (node (ref "C19") (pin "1") (pinfunction "1_1") (pintype "passive"))
      (node (ref "C2") (pin "1") (pinfunction "1_1") (pintype "passive"))
      (node (ref "C20") (pin "1") (pinfunction "1_1") (pintype "passive"))
      (node (ref "C21") (pin "1") (pinfunction "1_1") (pintype "passive"))
      (node (ref "C23") (pin "1") (pinfunction "1_1") (pintype "passive"))
      (node (ref "C24") (pin "1") (pinfunction "1_1") (pintype "passive"))
      (node (ref "C26") (pin "1") (pinfunction "1_1") (pintype "passive"))
      (node (ref "C27") (pin "1") (pinfunction "1_1") (pintype "passive"))
      (node (ref "C28") (pin "1") (pinfunction "1_1") (pintype "passive"))
      (node (ref "C3") (pin "1") (pinfunction "1_1") (pintype "passive"))
      (node (ref "C30") (pin "1") (pinfunction "1_1") (pintype "passive"))
      (node (ref "C31") (pin "1") (pinfunction "1_1") (pintype "passive"))
      (node (ref "C33") (pin "1") (pinfunction "1_1") (pintype "passive"))
      (node (ref "C34") (pin "1") (pinfunction "1_1") (pintype "passive"))
      (node (ref "C35") (pin "1") (pinfunction "1_1") (pintype "passive"))
      (node (ref "C37") (pin "1") (pinfunction "1_1") (pintype "passive"))
      (node (ref "C38") (pin "1") (pinfunction "1_1") (pintype "passive"))
      (node (ref "C40") (pin "1") (pinfunction "1_1") (pintype "passive"))
      (node (ref "C41") (pin "1") (pinfunction "1_1") (pintype "passive"))
      (node (ref "C42") (pin "1") (pinfunction "1_1") (pintype "passive"))
      (node (ref "C43") (pin "1") (pinfunction "1_1") (pintype "passive"))
      (node (ref "C44") (pin "1") (pinfunction "1_1") (pintype "passive"))
      (node (ref "C45") (pin "1") (pinfunction "1_1") (pintype "passive"))
      (node (ref "C46") (pin "1") (pinfunction "1_1") (pintype "passive"))
      (node (ref "C47") (pin "1") (pinfunction "1_1") (pintype "passive"))
      (node (ref "C48") (pin "1") (pinfunction "1_1") (pintype "passive"))
      (node (ref "C5") (pin "1") (pinfunction "1_1") (pintype "passive"))
      (node (ref "C6") (pin "1") (pinfunction "1_1") (pintype "passive"))
      (node (ref "C7") (pin "1") (pinfunction "1_1") (pintype "passive"))
      (node (ref "C9") (pin "1") (pinfunction "1_1") (pintype "passive"))
      (node (ref "CS1") (pin "2") (pinfunction "-_2") (pintype "passive"))
      (node (ref "D1") (pin "2") (pinfunction "A_2") (pintype "passive"))
      (node (ref "D2") (pin "2") (pinfunction "A_2") (pintype "passive"))
      (node (ref "D3") (pin "2") (pinfunction "A_2") (pintype "passive"))
      (node (ref "D4") (pin "2") (pinfunction "A_2") (pintype "passive"))
      (node (ref "D5") (pin "2") (pinfunction "A_2") (pintype "passive"))
      (node (ref "IC1") (pin "9") (pinfunction "PGND_9") (pintype "passive"))
      (node (ref "IC2") (pin "9") (pinfunction "PGND_9") (pintype "passive"))
      (node (ref "IC3") (pin "9") (pinfunction "PGND_9") (pintype "passive"))
      (node (ref "IC4") (pin "9") (pinfunction "PGND_9") (pintype "passive"))
      (node (ref "IC5") (pin "9") (pinfunction "PGND_9") (pintype "passive"))
      (node (ref "J1") (pin "N") (pinfunction "N_N") (pintype "power_in"))
      (node (ref "J10") (pin "2") (pinfunction "2_2") (pintype "passive"))
      (node (ref "J11") (pin "2") (pinfunction "2_2") (pintype "passive"))
      (node (ref "J12") (pin "2") (pinfunction "2_2") (pintype "passive"))
      (node (ref "J13") (pin "2") (pinfunction "2_2") (pintype "passive"))
      (node (ref "J14") (pin "2") (pinfunction "2_2") (pintype "passive"))
      (node (ref "J15") (pin "P") (pinfunction "P_P") (pintype "power_in"))
      (node (ref "J16") (pin "P") (pinfunction "P_P") (pintype "power_in"))
      (node (ref "J17") (pin "2") (pinfunction "2_2") (pintype "passive"))
      (node (ref "J18") (pin "2") (pinfunction "2_2") (pintype "passive"))
      (node (ref "J2") (pin "2") (pinfunction "2_2") (pintype "passive"))
      (node (ref "J3") (pin "2") (pinfunction "2_2") (pintype "passive"))
      (node (ref "J4") (pin "2") (pinfunction "2_2") (pintype "passive"))
      (node (ref "J5") (pin "2") (pinfunction "2_2") (pintype "passive"))
      (node (ref "J6") (pin "2") (pinfunction "2_2") (pintype "passive"))
      (node (ref "J7") (pin "2") (pinfunction "2_2") (pintype "passive"))
      (node (ref "J8") (pin "2") (pinfunction "2_2") (pintype "passive"))
      (node (ref "J9") (pin "2") (pinfunction "2_2") (pintype "passive"))
      (node (ref "NT1") (pin "2") (pintype "passive"))
      (node (ref "NT2") (pin "2") (pintype "passive"))
      (node (ref "NT3") (pin "2") (pintype "passive"))
      (node (ref "NT4") (pin "2") (pintype "passive"))
      (node (ref "NT5") (pin "2") (pintype "passive"))
      (node (ref "Tp10") (pin "TP") (pinfunction "TP_TP") (pintype "passive"))
      (node (ref "Tp11") (pin "TP") (pinfunction "TP_TP") (pintype "passive"))
      (node (ref "Tp6") (pin "TP") (pinfunction "TP_TP") (pintype "passive"))
    )
    (net (code "7") (name "Net-(C5-Pad2)") (class "Default")
      (node (ref "C5") (pin "2") (pinfunction "2_2") (pintype "passive"))
      (node (ref "C6") (pin "2") (pinfunction "2_2") (pintype "passive"))
      (node (ref "L1") (pin "1") (pinfunction "1_1") (pintype "passive"))
      (node (ref "L2") (pin "1") (pinfunction "1_1") (pintype "passive"))
      (node (ref "R5") (pin "2") (pinfunction "2_2") (pintype "passive"))
    )
    (net (code "8") (name "Net-(C8-Pad1)") (class "Default")
      (node (ref "C8") (pin "1") (pinfunction "1_1") (pintype "passive"))
      (node (ref "R6") (pin "2") (pinfunction "2_2") (pintype "passive"))
    )
    (net (code "9") (name "Net-(C14-Pad2)") (class "Default")
      (node (ref "C14") (pin "2") (pinfunction "2_2") (pintype "passive"))
      (node (ref "C15") (pin "2") (pinfunction "2_2") (pintype "passive"))
      (node (ref "L3") (pin "1") (pinfunction "1_1") (pintype "passive"))
      (node (ref "L4") (pin "1") (pinfunction "1_1") (pintype "passive"))
      (node (ref "R11") (pin "2") (pinfunction "2_2") (pintype "passive"))
    )
    (net (code "10") (name "Net-(C17-Pad1)") (class "Default")
      (node (ref "C17") (pin "1") (pinfunction "1_1") (pintype "passive"))
      (node (ref "R12") (pin "2") (pinfunction "2_2") (pintype "passive"))
    )
    (net (code "11") (name "Net-(C23-Pad2)") (class "Default")
      (node (ref "C23") (pin "2") (pinfunction "2_2") (pintype "passive"))
      (node (ref "C24") (pin "2") (pinfunction "2_2") (pintype "passive"))
      (node (ref "J6") (pin "1") (pinfunction "1_1") (pintype "passive"))
      (node (ref "J7") (pin "1") (pinfunction "1_1") (pintype "passive"))
      (node (ref "L5") (pin "1") (pinfunction "1_1") (pintype "passive"))
      (node (ref "R17") (pin "2") (pinfunction "2_2") (pintype "passive"))
      (node (ref "Tp3") (pin "TP") (pinfunction "TP_TP") (pintype "passive"))
    )
    (net (code "12") (name "Net-(C25-Pad1)") (class "Default")
      (node (ref "C25") (pin "1") (pinfunction "1_1") (pintype "passive"))
      (node (ref "R18") (pin "2") (pinfunction "2_2") (pintype "passive"))
    )
    (net (code "13") (name "Net-(C30-Pad2)") (class "Default")
      (node (ref "C30") (pin "2") (pinfunction "2_2") (pintype "passive"))
      (node (ref "C31") (pin "2") (pinfunction "2_2") (pintype "passive"))
      (node (ref "J8") (pin "1") (pinfunction "1_1") (pintype "passive"))
      (node (ref "J9") (pin "1") (pinfunction "1_1") (pintype "passive"))
      (node (ref "L6") (pin "1") (pinfunction "1_1") (pintype "passive"))
      (node (ref "R23") (pin "2") (pinfunction "2_2") (pintype "passive"))
      (node (ref "Tp4") (pin "TP") (pinfunction "TP_TP") (pintype "passive"))
    )
    (net (code "14") (name "Net-(C32-Pad1)") (class "Default")
      (node (ref "C32") (pin "1") (pinfunction "1_1") (pintype "passive"))
      (node (ref "R24") (pin "2") (pinfunction "2_2") (pintype "passive"))
    )
    (net (code "15") (name "Net-(C37-Pad2)") (class "Default")
      (node (ref "C37") (pin "2") (pinfunction "2_2") (pintype "passive"))
      (node (ref "C38") (pin "2") (pinfunction "2_2") (pintype "passive"))
      (node (ref "J10") (pin "1") (pinfunction "1_1") (pintype "passive"))
      (node (ref "J11") (pin "1") (pinfunction "1_1") (pintype "passive"))
      (node (ref "J12") (pin "1") (pinfunction "1_1") (pintype "passive"))
      (node (ref "L7") (pin "1") (pinfunction "1_1") (pintype "passive"))
      (node (ref "R29") (pin "2") (pinfunction "2_2") (pintype "passive"))
      (node (ref "Tp5") (pin "TP") (pinfunction "TP_TP") (pintype "passive"))
    )
    (net (code "16") (name "Net-(C39-Pad1)") (class "Default")
      (node (ref "C39") (pin "1") (pinfunction "1_1") (pintype "passive"))
      (node (ref "R30") (pin "2") (pinfunction "2_2") (pintype "passive"))
    )
    (net (code "17") (name "Net-(D2-K)") (class "Default")
      (node (ref "C7") (pin "2") (pinfunction "2_2") (pintype "passive"))
      (node (ref "C9") (pin "2") (pinfunction "2_2") (pintype "passive"))
      (node (ref "D2") (pin "1") (pinfunction "K_1") (pintype "passive"))
      (node (ref "J2") (pin "1") (pinfunction "1_1") (pintype "passive"))
      (node (ref "J3") (pin "1") (pinfunction "1_1") (pintype "passive"))
      (node (ref "L2") (pin "2") (pinfunction "2_2") (pintype "passive"))
      (node (ref "Tp1") (pin "TP") (pinfunction "TP_TP") (pintype "passive"))
    )
    (net (code "18") (name "Net-(D3-K)") (class "Default")
      (node (ref "C16") (pin "2") (pinfunction "2_2") (pintype "passive"))
      (node (ref "C18") (pin "2") (pinfunction "2_2") (pintype "passive"))
      (node (ref "D3") (pin "1") (pinfunction "K_1") (pintype "passive"))
      (node (ref "J4") (pin "1") (pinfunction "1_1") (pintype "passive"))
      (node (ref "J5") (pin "1") (pinfunction "1_1") (pintype "passive"))
      (node (ref "L4") (pin "2") (pinfunction "2_2") (pintype "passive"))
      (node (ref "Tp2") (pin "TP") (pinfunction "TP_TP") (pintype "passive"))
      (node (ref "Tp8") (pin "TP") (pinfunction "TP_TP") (pintype "passive"))
      (node (ref "Tp9") (pin "TP") (pinfunction "TP_TP") (pintype "passive"))
    )
    (net (code "19") (name "Net-(IC1-BOOT)") (class "Default")
      (node (ref "C4") (pin "1") (pinfunction "1_1") (pintype "passive"))
      (node (ref "IC1") (pin "7") (pinfunction "BOOT_7") (pintype "passive"))
    )
    (net (code "20") (name "Net-(IC1-EN)") (class "Default")
      (node (ref "IC1") (pin "1") (pinfunction "EN_1") (pintype "passive"))
      (node (ref "R1") (pin "1") (pinfunction "1_1") (pintype "passive"))
      (node (ref "R4") (pin "2") (pinfunction "2_2") (pintype "passive"))
    )
    (net (code "21") (name "Net-(IC1-FB)") (class "Default")
      (node (ref "C8") (pin "2") (pinfunction "2_2") (pintype "passive"))
      (node (ref "IC1") (pin "2") (pinfunction "FB_2") (pintype "passive"))
      (node (ref "R7") (pin "1") (pinfunction "1_1") (pintype "passive"))
      (node (ref "R8") (pin "2") (pinfunction "2_2") (pintype "passive"))
    )
    (net (code "22") (name "Net-(IC1-SW)") (class "Default")
      (node (ref "C4") (pin "2") (pinfunction "2_2") (pintype "passive"))
      (node (ref "IC1") (pin "6") (pinfunction "SW_6") (pintype "passive"))
      (node (ref "L1") (pin "2") (pinfunction "2_2") (pintype "passive"))
    )
    (net (code "23") (name "Net-(IC2-BOOT)") (class "Default")
      (node (ref "C13") (pin "1") (pinfunction "1_1") (pintype "passive"))
      (node (ref "IC2") (pin "7") (pinfunction "BOOT_7") (pintype "passive"))
    )
    (net (code "24") (name "Net-(IC2-EN)") (class "Default")
      (node (ref "IC2") (pin "1") (pinfunction "EN_1") (pintype "passive"))
      (node (ref "R10") (pin "2") (pinfunction "2_2") (pintype "passive"))
      (node (ref "R9") (pin "1") (pinfunction "1_1") (pintype "passive"))
    )
    (net (code "25") (name "Net-(IC2-FB)") (class "Default")
      (node (ref "C17") (pin "2") (pinfunction "2_2") (pintype "passive"))
      (node (ref "IC2") (pin "2") (pinfunction "FB_2") (pintype "passive"))
      (node (ref "R13") (pin "1") (pinfunction "1_1") (pintype "passive"))
      (node (ref "R14") (pin "2") (pinfunction "2_2") (pintype "passive"))
    )
    (net (code "26") (name "Net-(IC2-SW)") (class "Default")
      (node (ref "C13") (pin "2") (pinfunction "2_2") (pintype "passive"))
      (node (ref "IC2") (pin "6") (pinfunction "SW_6") (pintype "passive"))
      (node (ref "L3") (pin "2") (pinfunction "2_2") (pintype "passive"))
    )
    (net (code "27") (name "Net-(IC3-BOOT)") (class "Default")
      (node (ref "C22") (pin "1") (pinfunction "1_1") (pintype "passive"))
      (node (ref "IC3") (pin "7") (pinfunction "BOOT_7") (pintype "passive"))
    )
    (net (code "28") (name "Net-(IC3-EN)") (class "Default")
      (node (ref "IC3") (pin "1") (pinfunction "EN_1") (pintype "passive"))
      (node (ref "R15") (pin "1") (pinfunction "1_1") (pintype "passive"))
      (node (ref "R16") (pin "2") (pinfunction "2_2") (pintype "passive"))
    )
    (net (code "29") (name "Net-(IC3-FB)") (class "Default")
      (node (ref "C25") (pin "2") (pinfunction "2_2") (pintype "passive"))
      (node (ref "IC3") (pin "2") (pinfunction "FB_2") (pintype "passive"))
      (node (ref "P1") (pin "1") (pinfunction "CCW_1") (pintype "passive"))
      (node (ref "P1") (pin "2") (pinfunction "WIPER_2") (pintype "passive"))
      (node (ref "R20") (pin "2") (pinfunction "2_2") (pintype "passive"))
    )
    (net (code "30") (name "Net-(IC3-SW)") (class "Default")
      (node (ref "C22") (pin "2") (pinfunction "2_2") (pintype "passive"))
      (node (ref "IC3") (pin "6") (pinfunction "SW_6") (pintype "passive"))
      (node (ref "L5") (pin "2") (pinfunction "2_2") (pintype "passive"))
    )
    (net (code "31") (name "Net-(IC4-BOOT)") (class "Default")
      (node (ref "C29") (pin "1") (pinfunction "1_1") (pintype "passive"))
      (node (ref "IC4") (pin "7") (pinfunction "BOOT_7") (pintype "passive"))
    )
    (net (code "32") (name "Net-(IC4-EN)") (class "Default")
      (node (ref "IC4") (pin "1") (pinfunction "EN_1") (pintype "passive"))
      (node (ref "R21") (pin "1") (pinfunction "1_1") (pintype "passive"))
      (node (ref "R22") (pin "2") (pinfunction "2_2") (pintype "passive"))
    )
    (net (code "33") (name "Net-(IC4-FB)") (class "Default")
      (node (ref "C32") (pin "2") (pinfunction "2_2") (pintype "passive"))
      (node (ref "IC4") (pin "2") (pinfunction "FB_2") (pintype "passive"))
      (node (ref "P2") (pin "1") (pinfunction "CCW_1") (pintype "passive"))
      (node (ref "P2") (pin "2") (pinfunction "WIPER_2") (pintype "passive"))
      (node (ref "R26") (pin "2") (pinfunction "2_2") (pintype "passive"))
    )
    (net (code "34") (name "Net-(IC4-SW)") (class "Default")
      (node (ref "C29") (pin "2") (pinfunction "2_2") (pintype "passive"))
      (node (ref "IC4") (pin "6") (pinfunction "SW_6") (pintype "passive"))
      (node (ref "L6") (pin "2") (pinfunction "2_2") (pintype "passive"))
    )
    (net (code "35") (name "Net-(IC5-BOOT)") (class "Default")
      (node (ref "C36") (pin "1") (pinfunction "1_1") (pintype "passive"))
      (node (ref "IC5") (pin "7") (pinfunction "BOOT_7") (pintype "passive"))
    )
    (net (code "36") (name "Net-(IC5-EN)") (class "Default")
      (node (ref "IC5") (pin "1") (pinfunction "EN_1") (pintype "passive"))
      (node (ref "R27") (pin "1") (pinfunction "1_1") (pintype "passive"))
      (node (ref "R28") (pin "2") (pinfunction "2_2") (pintype "passive"))
    )
    (net (code "37") (name "Net-(IC5-FB)") (class "Default")
      (node (ref "C39") (pin "2") (pinfunction "2_2") (pintype "passive"))
      (node (ref "IC5") (pin "2") (pinfunction "FB_2") (pintype "passive"))
      (node (ref "R31") (pin "1") (pinfunction "1_1") (pintype "passive"))
      (node (ref "R32") (pin "2") (pinfunction "2_2") (pintype "passive"))
    )
    (net (code "38") (name "Net-(IC5-SW)") (class "Default")
      (node (ref "C36") (pin "2") (pinfunction "2_2") (pintype "passive"))
      (node (ref "IC5") (pin "6") (pinfunction "SW_6") (pintype "passive"))
      (node (ref "L7") (pin "2") (pinfunction "2_2") (pintype "passive"))
    )
    (net (code "39") (name "Net-(P1-CW)") (class "Default")
      (node (ref "P1") (pin "3") (pinfunction "CW_3") (pintype "passive"))
      (node (ref "R19") (pin "1") (pinfunction "1_1") (pintype "passive"))
    )
    (net (code "40") (name "Net-(P2-CW)") (class "Default")
      (node (ref "P2") (pin "3") (pinfunction "CW_3") (pintype "passive"))
      (node (ref "R25") (pin "1") (pinfunction "1_1") (pintype "passive"))
    )
    (net (code "41") (name "Net-(R5-Pad1)") (class "Default")
      (node (ref "R5") (pin "1") (pinfunction "1_1") (pintype "passive"))
      (node (ref "R6") (pin "1") (pinfunction "1_1") (pintype "passive"))
      (node (ref "R7") (pin "2") (pinfunction "2_2") (pintype "passive"))
    )
    (net (code "42") (name "Net-(R11-Pad1)") (class "Default")
      (node (ref "R11") (pin "1") (pinfunction "1_1") (pintype "passive"))
      (node (ref "R12") (pin "1") (pinfunction "1_1") (pintype "passive"))
      (node (ref "R13") (pin "2") (pinfunction "2_2") (pintype "passive"))
    )
    (net (code "43") (name "Net-(R17-Pad1)") (class "Default")
      (node (ref "R17") (pin "1") (pinfunction "1_1") (pintype "passive"))
      (node (ref "R18") (pin "1") (pinfunction "1_1") (pintype "passive"))
      (node (ref "R19") (pin "2") (pinfunction "2_2") (pintype "passive"))
    )
    (net (code "44") (name "Net-(R23-Pad1)") (class "Default")
      (node (ref "R23") (pin "1") (pinfunction "1_1") (pintype "passive"))
      (node (ref "R24") (pin "1") (pinfunction "1_1") (pintype "passive"))
      (node (ref "R25") (pin "2") (pinfunction "2_2") (pintype "passive"))
    )
    (net (code "45") (name "Net-(R29-Pad1)") (class "Default")
      (node (ref "R29") (pin "1") (pinfunction "1_1") (pintype "passive"))
      (node (ref "R30") (pin "1") (pinfunction "1_1") (pintype "passive"))
      (node (ref "R31") (pin "2") (pinfunction "2_2") (pintype "passive"))
    )
    (net (code "46") (name "VCC") (class "Default")
      (node (ref "C1") (pin "2") (pinfunction "2_2") (pintype "passive"))
      (node (ref "C10") (pin "2") (pinfunction "2_2") (pintype "passive"))
      (node (ref "C11") (pin "2") (pinfunction "2_2") (pintype "passive"))
      (node (ref "C12") (pin "2") (pinfunction "2_2") (pintype "passive"))
      (node (ref "C19") (pin "2") (pinfunction "2_2") (pintype "passive"))
      (node (ref "C2") (pin "2") (pinfunction "2_2") (pintype "passive"))
      (node (ref "C20") (pin "2") (pinfunction "2_2") (pintype "passive"))
      (node (ref "C21") (pin "2") (pinfunction "2_2") (pintype "passive"))
      (node (ref "C26") (pin "2") (pinfunction "2_2") (pintype "passive"))
      (node (ref "C27") (pin "2") (pinfunction "2_2") (pintype "passive"))
      (node (ref "C28") (pin "2") (pinfunction "2_2") (pintype "passive"))
      (node (ref "C3") (pin "2") (pinfunction "2_2") (pintype "passive"))
      (node (ref "C33") (pin "2") (pinfunction "2_2") (pintype "passive"))
      (node (ref "C34") (pin "2") (pinfunction "2_2") (pintype "passive"))
      (node (ref "C35") (pin "2") (pinfunction "2_2") (pintype "passive"))
      (node (ref "C40") (pin "2") (pinfunction "2_2") (pintype "passive"))
      (node (ref "C41") (pin "2") (pinfunction "2_2") (pintype "passive"))
      (node (ref "C42") (pin "2") (pinfunction "2_2") (pintype "passive"))
      (node (ref "C43") (pin "2") (pinfunction "2_2") (pintype "passive"))
      (node (ref "C44") (pin "2") (pinfunction "2_2") (pintype "passive"))
      (node (ref "C45") (pin "2") (pinfunction "2_2") (pintype "passive"))
      (node (ref "C46") (pin "2") (pinfunction "2_2") (pintype "passive"))
      (node (ref "C47") (pin "2") (pinfunction "2_2") (pintype "passive"))
      (node (ref "C48") (pin "2") (pinfunction "2_2") (pintype "passive"))
      (node (ref "CS1") (pin "1") (pinfunction "+_1") (pintype "passive"))
      (node (ref "D1") (pin "1") (pinfunction "K_1") (pintype "passive"))
      (node (ref "D4") (pin "1") (pinfunction "K_1") (pintype "passive"))
      (node (ref "D5") (pin "1") (pinfunction "K_1") (pintype "passive"))
      (node (ref "IC1") (pin "11") (pinfunction "VIN_2_11") (pintype "passive"))
      (node (ref "IC1") (pin "12") (pinfunction "VIN_3_12") (pintype "passive"))
      (node (ref "IC1") (pin "13") (pinfunction "VIN_4_13") (pintype "passive"))
      (node (ref "IC1") (pin "8") (pinfunction "VIN_1_8") (pintype "passive"))
      (node (ref "IC2") (pin "11") (pinfunction "VIN_2_11") (pintype "passive"))
      (node (ref "IC2") (pin "12") (pinfunction "VIN_3_12") (pintype "passive"))
      (node (ref "IC2") (pin "13") (pinfunction "VIN_4_13") (pintype "passive"))
      (node (ref "IC2") (pin "8") (pinfunction "VIN_1_8") (pintype "passive"))
      (node (ref "IC3") (pin "11") (pinfunction "VIN_2_11") (pintype "passive"))
      (node (ref "IC3") (pin "12") (pinfunction "VIN_3_12") (pintype "passive"))
      (node (ref "IC3") (pin "13") (pinfunction "VIN_4_13") (pintype "passive"))
      (node (ref "IC3") (pin "8") (pinfunction "VIN_1_8") (pintype "passive"))
      (node (ref "IC4") (pin "11") (pinfunction "VIN_2_11") (pintype "passive"))
      (node (ref "IC4") (pin "12") (pinfunction "VIN_3_12") (pintype "passive"))
      (node (ref "IC4") (pin "13") (pinfunction "VIN_4_13") (pintype "passive"))
      (node (ref "IC4") (pin "8") (pinfunction "VIN_1_8") (pintype "passive"))
      (node (ref "IC5") (pin "11") (pinfunction "VIN_2_11") (pintype "passive"))
      (node (ref "IC5") (pin "12") (pinfunction "VIN_3_12") (pintype "passive"))
      (node (ref "IC5") (pin "13") (pinfunction "VIN_4_13") (pintype "passive"))
      (node (ref "IC5") (pin "8") (pinfunction "VIN_1_8") (pintype "passive"))
      (node (ref "J1") (pin "P") (pinfunction "P_P") (pintype "power_in"))
      (node (ref "J13") (pin "1") (pinfunction "1_1") (pintype "passive"))
      (node (ref "J14") (pin "1") (pinfunction "1_1") (pintype "passive"))
      (node (ref "J15") (pin "N") (pinfunction "N_N") (pintype "power_in"))
      (node (ref "J16") (pin "N") (pinfunction "N_N") (pintype "power_in"))
      (node (ref "J17") (pin "1") (pinfunction "1_1") (pintype "passive"))
      (node (ref "J18") (pin "1") (pinfunction "1_1") (pintype "passive"))
      (node (ref "R1") (pin "2") (pinfunction "2_2") (pintype "passive"))
      (node (ref "R15") (pin "2") (pinfunction "2_2") (pintype "passive"))
      (node (ref "R21") (pin "2") (pinfunction "2_2") (pintype "passive"))
      (node (ref "R27") (pin "2") (pinfunction "2_2") (pintype "passive"))
      (node (ref "R9") (pin "2") (pinfunction "2_2") (pintype "passive"))
      (node (ref "Tp7") (pin "TP") (pinfunction "TP_TP") (pintype "passive"))
    )
    (net (code "47") (name "unconnected-(IC1-NC-Pad5)") (class "Default")
      (node (ref "IC1") (pin "5") (pinfunction "NC_5") (pintype "passive+no_connect"))
    )
    (net (code "48") (name "unconnected-(IC1-PG-Pad4)") (class "Default")
      (node (ref "IC1") (pin "4") (pinfunction "PG_4") (pintype "passive+no_connect"))
    )
    (net (code "49") (name "unconnected-(IC2-NC-Pad5)") (class "Default")
      (node (ref "IC2") (pin "5") (pinfunction "NC_5") (pintype "passive+no_connect"))
    )
    (net (code "50") (name "unconnected-(IC2-PG-Pad4)") (class "Default")
      (node (ref "IC2") (pin "4") (pinfunction "PG_4") (pintype "passive+no_connect"))
    )
    (net (code "51") (name "unconnected-(IC3-NC-Pad5)") (class "Default")
      (node (ref "IC3") (pin "5") (pinfunction "NC_5") (pintype "passive+no_connect"))
    )
    (net (code "52") (name "unconnected-(IC3-PG-Pad4)") (class "Default")
      (node (ref "IC3") (pin "4") (pinfunction "PG_4") (pintype "passive+no_connect"))
    )
    (net (code "53") (name "unconnected-(IC4-NC-Pad5)") (class "Default")
      (node (ref "IC4") (pin "5") (pinfunction "NC_5") (pintype "passive+no_connect"))
    )
    (net (code "54") (name "unconnected-(IC4-PG-Pad4)") (class "Default")
      (node (ref "IC4") (pin "4") (pinfunction "PG_4") (pintype "passive+no_connect"))
    )
    (net (code "55") (name "unconnected-(IC5-NC-Pad5)") (class "Default")
      (node (ref "IC5") (pin "5") (pinfunction "NC_5") (pintype "passive+no_connect"))
    )
    (net (code "56") (name "unconnected-(IC5-PG-Pad4)") (class "Default")
      (node (ref "IC5") (pin "4") (pinfunction "PG_4") (pintype "passive+no_connect"))
    )
  )
)
